# Sheet1.net
KiCad netlist of a schematic drawn in Altium Designer
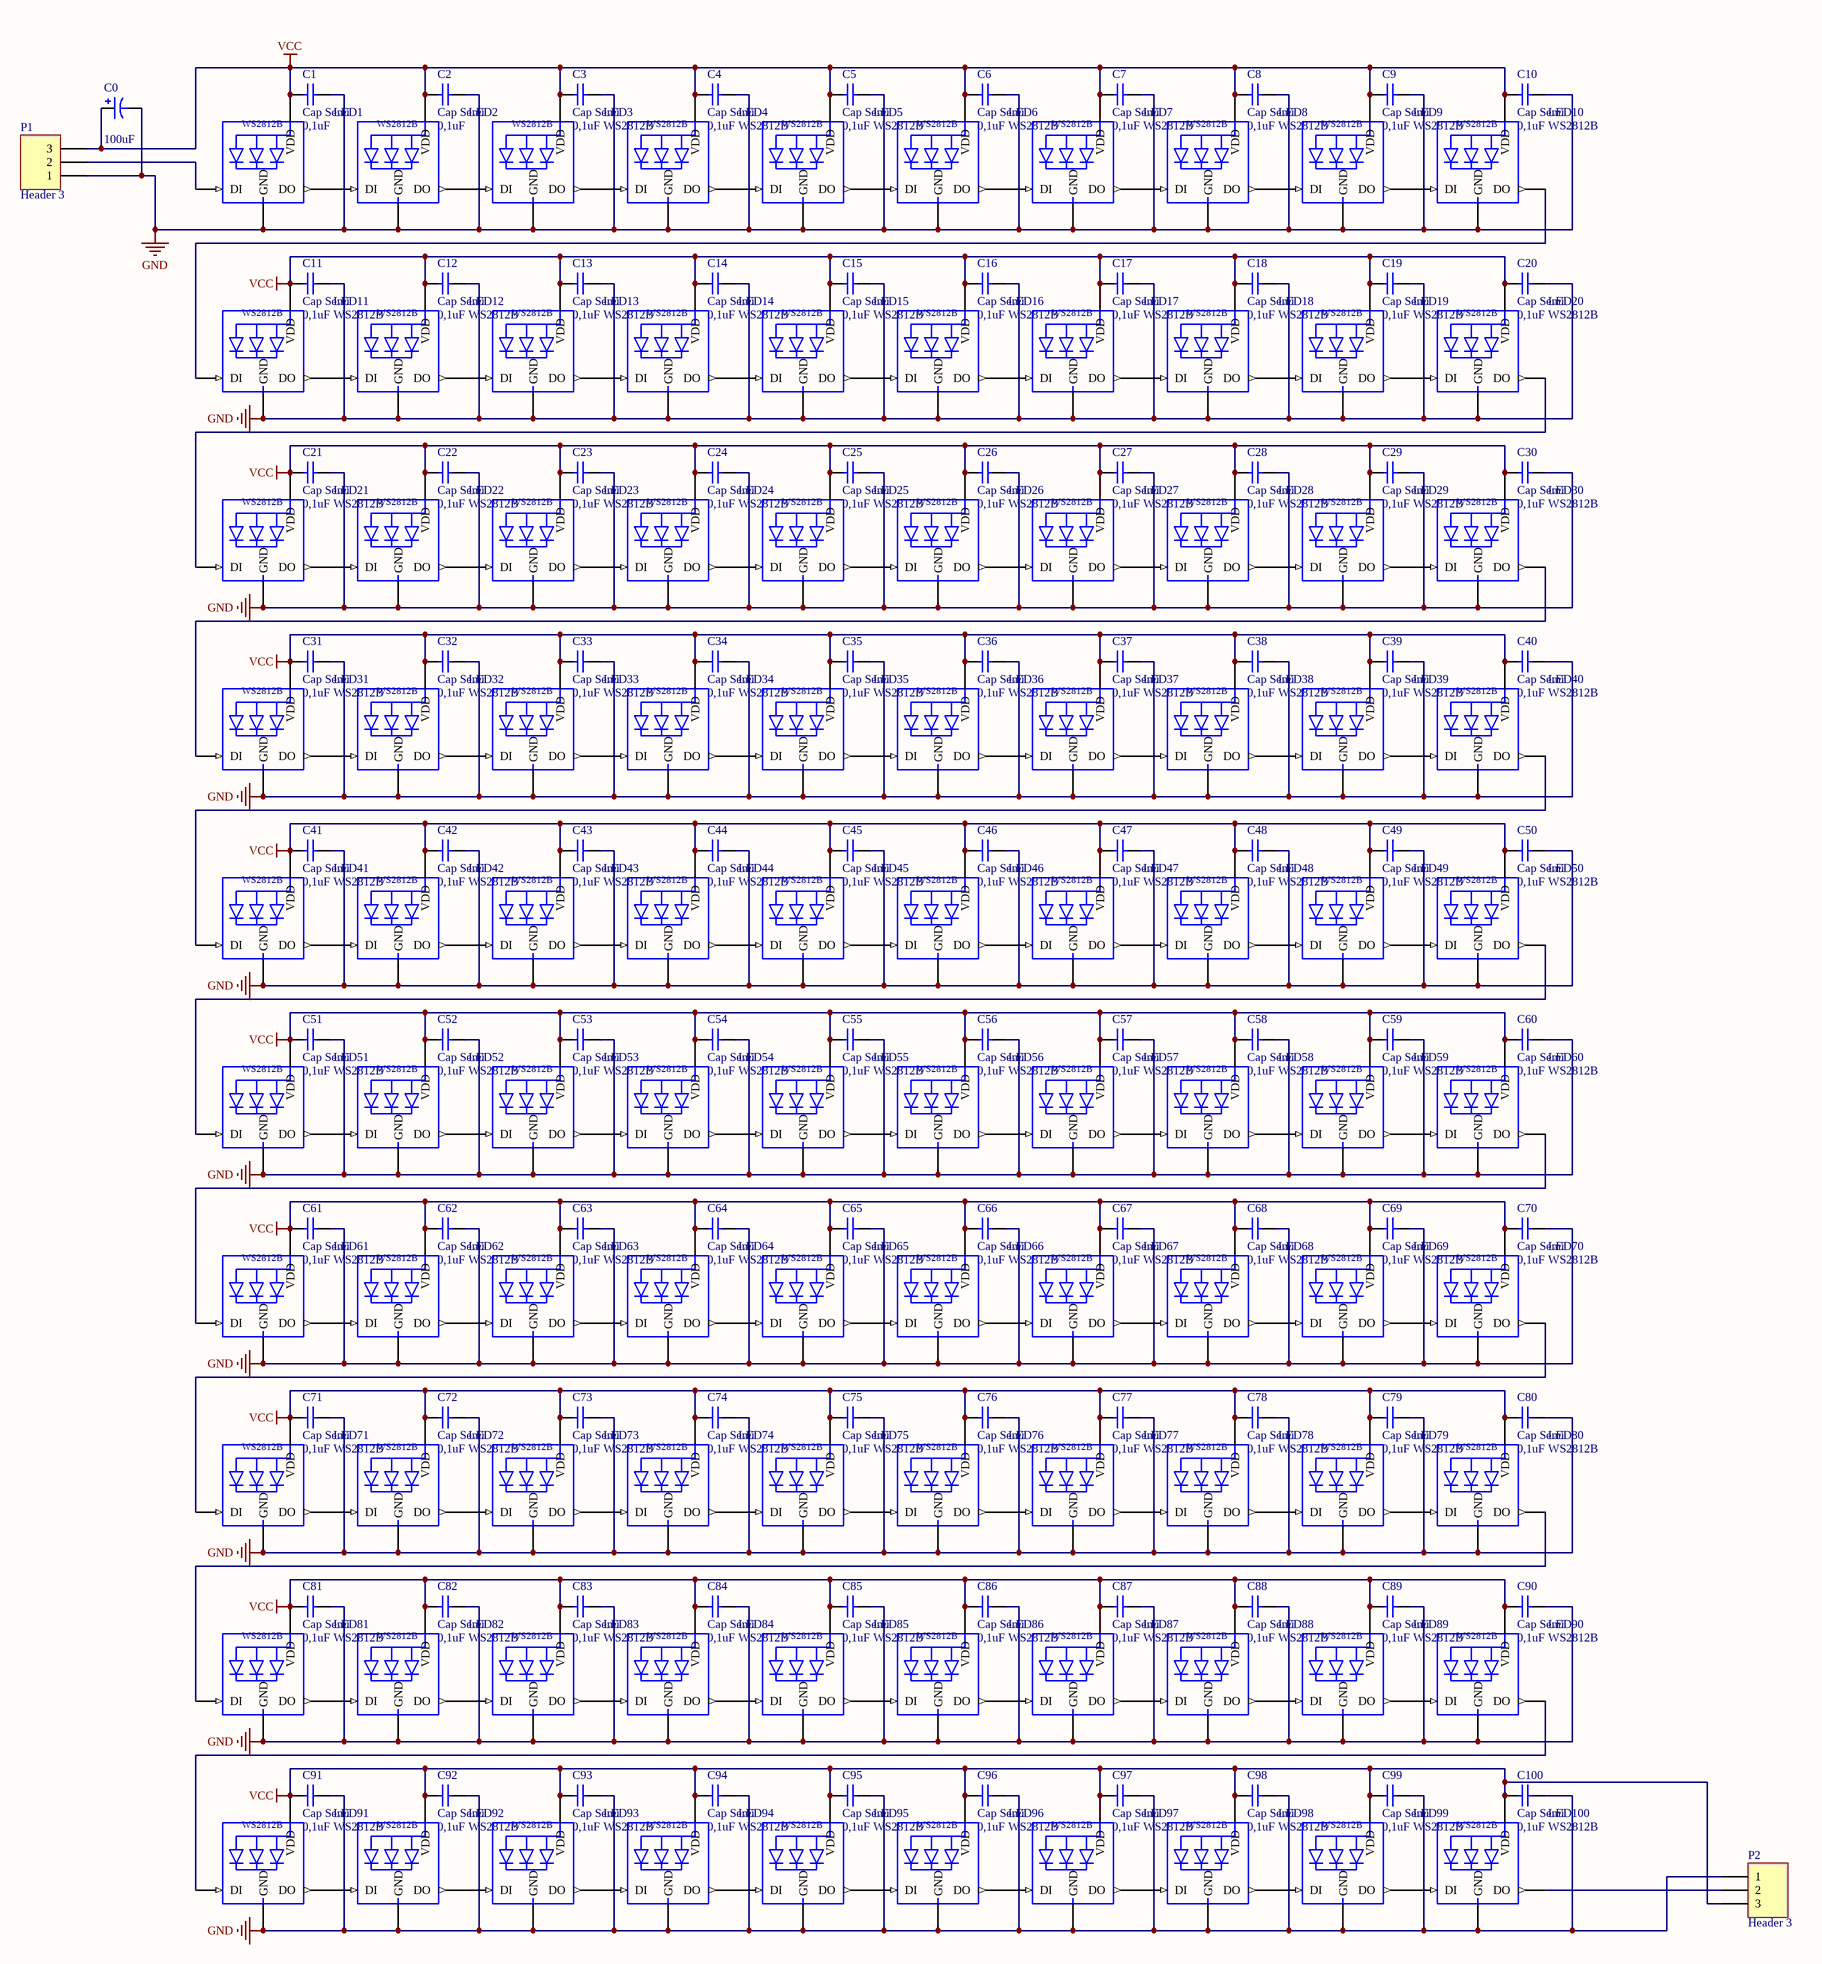
[diagram p0: Sheet1.SchDoc]

(export (version "E")
  (design (tool "Eeschema 10.0.6"))
  (components
    (comp (ref "C0")
      (value "100uF")
      (footprint "RB7.6-15")
      (description "Polarized Capacitor (Radial)")
      (fields (field (name "Comment") "Cap Pol1") (field (name "PUBLISHER") "Altium Limited"))
      (libsource (lib "Miscellaneous Devices") (part "Cap Pol1"))
    )
    (comp (ref "C1")
      (value "Cap Semi")
      (footprint "1608[0603]")
      (description "Capacitor (Semiconductor SIM Model)")
      (fields (field (name "ALTIUM_VALUE") "0,1uF") (field (name "PUBLISHER") "Altium Limited"))
      (libsource (lib "Miscellaneous Devices") (part "Cap Semi"))
    )
    (comp (ref "C2")
      (value "Cap Semi")
      (footprint "1608[0603]")
      (description "Capacitor (Semiconductor SIM Model)")
      (fields (field (name "ALTIUM_VALUE") "0,1uF") (field (name "PUBLISHER") "Altium Limited"))
      (libsource (lib "Miscellaneous Devices") (part "Cap Semi"))
    )
    (comp (ref "C3")
      (value "Cap Semi")
      (footprint "1608[0603]")
      (description "Capacitor (Semiconductor SIM Model)")
      (fields (field (name "ALTIUM_VALUE") "0,1uF") (field (name "PUBLISHER") "Altium Limited"))
      (libsource (lib "Miscellaneous Devices") (part "Cap Semi"))
    )
    (comp (ref "C4")
      (value "Cap Semi")
      (footprint "1608[0603]")
      (description "Capacitor (Semiconductor SIM Model)")
      (fields (field (name "ALTIUM_VALUE") "0,1uF") (field (name "PUBLISHER") "Altium Limited"))
      (libsource (lib "Miscellaneous Devices") (part "Cap Semi"))
    )
    (comp (ref "C5")
      (value "Cap Semi")
      (footprint "1608[0603]")
      (description "Capacitor (Semiconductor SIM Model)")
      (fields (field (name "ALTIUM_VALUE") "0,1uF") (field (name "PUBLISHER") "Altium Limited"))
      (libsource (lib "Miscellaneous Devices") (part "Cap Semi"))
    )
    (comp (ref "C6")
      (value "Cap Semi")
      (footprint "1608[0603]")
      (description "Capacitor (Semiconductor SIM Model)")
      (fields (field (name "ALTIUM_VALUE") "0,1uF") (field (name "PUBLISHER") "Altium Limited"))
      (libsource (lib "Miscellaneous Devices") (part "Cap Semi"))
    )
    (comp (ref "C7")
      (value "Cap Semi")
      (footprint "1608[0603]")
      (description "Capacitor (Semiconductor SIM Model)")
      (fields (field (name "ALTIUM_VALUE") "0,1uF") (field (name "PUBLISHER") "Altium Limited"))
      (libsource (lib "Miscellaneous Devices") (part "Cap Semi"))
    )
    (comp (ref "C8")
      (value "Cap Semi")
      (footprint "1608[0603]")
      (description "Capacitor (Semiconductor SIM Model)")
      (fields (field (name "ALTIUM_VALUE") "0,1uF") (field (name "PUBLISHER") "Altium Limited"))
      (libsource (lib "Miscellaneous Devices") (part "Cap Semi"))
    )
    (comp (ref "C9")
      (value "Cap Semi")
      (footprint "1608[0603]")
      (description "Capacitor (Semiconductor SIM Model)")
      (fields (field (name "ALTIUM_VALUE") "0,1uF") (field (name "PUBLISHER") "Altium Limited"))
      (libsource (lib "Miscellaneous Devices") (part "Cap Semi"))
    )
    (comp (ref "C10")
      (value "Cap Semi")
      (footprint "1608[0603]")
      (description "Capacitor (Semiconductor SIM Model)")
      (fields (field (name "ALTIUM_VALUE") "0,1uF") (field (name "PUBLISHER") "Altium Limited"))
      (libsource (lib "Miscellaneous Devices") (part "Cap Semi"))
    )
    (comp (ref "C11")
      (value "Cap Semi")
      (footprint "1608[0603]")
      (description "Capacitor (Semiconductor SIM Model)")
      (fields (field (name "ALTIUM_VALUE") "0,1uF") (field (name "PUBLISHER") "Altium Limited"))
      (libsource (lib "Miscellaneous Devices") (part "Cap Semi"))
    )
    (comp (ref "C12")
      (value "Cap Semi")
      (footprint "1608[0603]")
      (description "Capacitor (Semiconductor SIM Model)")
      (fields (field (name "ALTIUM_VALUE") "0,1uF") (field (name "PUBLISHER") "Altium Limited"))
      (libsource (lib "Miscellaneous Devices") (part "Cap Semi"))
    )
    (comp (ref "C13")
      (value "Cap Semi")
      (footprint "1608[0603]")
      (description "Capacitor (Semiconductor SIM Model)")
      (fields (field (name "ALTIUM_VALUE") "0,1uF") (field (name "PUBLISHER") "Altium Limited"))
      (libsource (lib "Miscellaneous Devices") (part "Cap Semi"))
    )
    (comp (ref "C14")
      (value "Cap Semi")
      (footprint "1608[0603]")
      (description "Capacitor (Semiconductor SIM Model)")
      (fields (field (name "ALTIUM_VALUE") "0,1uF") (field (name "PUBLISHER") "Altium Limited"))
      (libsource (lib "Miscellaneous Devices") (part "Cap Semi"))
    )
    (comp (ref "C15")
      (value "Cap Semi")
      (footprint "1608[0603]")
      (description "Capacitor (Semiconductor SIM Model)")
      (fields (field (name "ALTIUM_VALUE") "0,1uF") (field (name "PUBLISHER") "Altium Limited"))
      (libsource (lib "Miscellaneous Devices") (part "Cap Semi"))
    )
    (comp (ref "C16")
      (value "Cap Semi")
      (footprint "1608[0603]")
      (description "Capacitor (Semiconductor SIM Model)")
      (fields (field (name "ALTIUM_VALUE") "0,1uF") (field (name "PUBLISHER") "Altium Limited"))
      (libsource (lib "Miscellaneous Devices") (part "Cap Semi"))
    )
    (comp (ref "C17")
      (value "Cap Semi")
      (footprint "1608[0603]")
      (description "Capacitor (Semiconductor SIM Model)")
      (fields (field (name "ALTIUM_VALUE") "0,1uF") (field (name "PUBLISHER") "Altium Limited"))
      (libsource (lib "Miscellaneous Devices") (part "Cap Semi"))
    )
    (comp (ref "C18")
      (value "Cap Semi")
      (footprint "1608[0603]")
      (description "Capacitor (Semiconductor SIM Model)")
      (fields (field (name "ALTIUM_VALUE") "0,1uF") (field (name "PUBLISHER") "Altium Limited"))
      (libsource (lib "Miscellaneous Devices") (part "Cap Semi"))
    )
    (comp (ref "C19")
      (value "Cap Semi")
      (footprint "1608[0603]")
      (description "Capacitor (Semiconductor SIM Model)")
      (fields (field (name "ALTIUM_VALUE") "0,1uF") (field (name "PUBLISHER") "Altium Limited"))
      (libsource (lib "Miscellaneous Devices") (part "Cap Semi"))
    )
    (comp (ref "C20")
      (value "Cap Semi")
      (footprint "1608[0603]")
      (description "Capacitor (Semiconductor SIM Model)")
      (fields (field (name "ALTIUM_VALUE") "0,1uF") (field (name "PUBLISHER") "Altium Limited"))
      (libsource (lib "Miscellaneous Devices") (part "Cap Semi"))
    )
    (comp (ref "C21")
      (value "Cap Semi")
      (footprint "1608[0603]")
      (description "Capacitor (Semiconductor SIM Model)")
      (fields (field (name "ALTIUM_VALUE") "0,1uF") (field (name "PUBLISHER") "Altium Limited"))
      (libsource (lib "Miscellaneous Devices") (part "Cap Semi"))
    )
    (comp (ref "C22")
      (value "Cap Semi")
      (footprint "1608[0603]")
      (description "Capacitor (Semiconductor SIM Model)")
      (fields (field (name "ALTIUM_VALUE") "0,1uF") (field (name "PUBLISHER") "Altium Limited"))
      (libsource (lib "Miscellaneous Devices") (part "Cap Semi"))
    )
    (comp (ref "C23")
      (value "Cap Semi")
      (footprint "1608[0603]")
      (description "Capacitor (Semiconductor SIM Model)")
      (fields (field (name "ALTIUM_VALUE") "0,1uF") (field (name "PUBLISHER") "Altium Limited"))
      (libsource (lib "Miscellaneous Devices") (part "Cap Semi"))
    )
    (comp (ref "C24")
      (value "Cap Semi")
      (footprint "1608[0603]")
      (description "Capacitor (Semiconductor SIM Model)")
      (fields (field (name "ALTIUM_VALUE") "0,1uF") (field (name "PUBLISHER") "Altium Limited"))
      (libsource (lib "Miscellaneous Devices") (part "Cap Semi"))
    )
    (comp (ref "C25")
      (value "Cap Semi")
      (footprint "1608[0603]")
      (description "Capacitor (Semiconductor SIM Model)")
      (fields (field (name "ALTIUM_VALUE") "0,1uF") (field (name "PUBLISHER") "Altium Limited"))
      (libsource (lib "Miscellaneous Devices") (part "Cap Semi"))
    )
    (comp (ref "C26")
      (value "Cap Semi")
      (footprint "1608[0603]")
      (description "Capacitor (Semiconductor SIM Model)")
      (fields (field (name "ALTIUM_VALUE") "0,1uF") (field (name "PUBLISHER") "Altium Limited"))
      (libsource (lib "Miscellaneous Devices") (part "Cap Semi"))
    )
    (comp (ref "C27")
      (value "Cap Semi")
      (footprint "1608[0603]")
      (description "Capacitor (Semiconductor SIM Model)")
      (fields (field (name "ALTIUM_VALUE") "0,1uF") (field (name "PUBLISHER") "Altium Limited"))
      (libsource (lib "Miscellaneous Devices") (part "Cap Semi"))
    )
    (comp (ref "C28")
      (value "Cap Semi")
      (footprint "1608[0603]")
      (description "Capacitor (Semiconductor SIM Model)")
      (fields (field (name "ALTIUM_VALUE") "0,1uF") (field (name "PUBLISHER") "Altium Limited"))
      (libsource (lib "Miscellaneous Devices") (part "Cap Semi"))
    )
    (comp (ref "C29")
      (value "Cap Semi")
      (footprint "1608[0603]")
      (description "Capacitor (Semiconductor SIM Model)")
      (fields (field (name "ALTIUM_VALUE") "0,1uF") (field (name "PUBLISHER") "Altium Limited"))
      (libsource (lib "Miscellaneous Devices") (part "Cap Semi"))
    )
    (comp (ref "C30")
      (value "Cap Semi")
      (footprint "1608[0603]")
      (description "Capacitor (Semiconductor SIM Model)")
      (fields (field (name "ALTIUM_VALUE") "0,1uF") (field (name "PUBLISHER") "Altium Limited"))
      (libsource (lib "Miscellaneous Devices") (part "Cap Semi"))
    )
    (comp (ref "C31")
      (value "Cap Semi")
      (footprint "1608[0603]")
      (description "Capacitor (Semiconductor SIM Model)")
      (fields (field (name "ALTIUM_VALUE") "0,1uF") (field (name "PUBLISHER") "Altium Limited"))
      (libsource (lib "Miscellaneous Devices") (part "Cap Semi"))
    )
    (comp (ref "C32")
      (value "Cap Semi")
      (footprint "1608[0603]")
      (description "Capacitor (Semiconductor SIM Model)")
      (fields (field (name "ALTIUM_VALUE") "0,1uF") (field (name "PUBLISHER") "Altium Limited"))
      (libsource (lib "Miscellaneous Devices") (part "Cap Semi"))
    )
    (comp (ref "C33")
      (value "Cap Semi")
      (footprint "1608[0603]")
      (description "Capacitor (Semiconductor SIM Model)")
      (fields (field (name "ALTIUM_VALUE") "0,1uF") (field (name "PUBLISHER") "Altium Limited"))
      (libsource (lib "Miscellaneous Devices") (part "Cap Semi"))
    )
    (comp (ref "C34")
      (value "Cap Semi")
      (footprint "1608[0603]")
      (description "Capacitor (Semiconductor SIM Model)")
      (fields (field (name "ALTIUM_VALUE") "0,1uF") (field (name "PUBLISHER") "Altium Limited"))
      (libsource (lib "Miscellaneous Devices") (part "Cap Semi"))
    )
    (comp (ref "C35")
      (value "Cap Semi")
      (footprint "1608[0603]")
      (description "Capacitor (Semiconductor SIM Model)")
      (fields (field (name "ALTIUM_VALUE") "0,1uF") (field (name "PUBLISHER") "Altium Limited"))
      (libsource (lib "Miscellaneous Devices") (part "Cap Semi"))
    )
    (comp (ref "C36")
      (value "Cap Semi")
      (footprint "1608[0603]")
      (description "Capacitor (Semiconductor SIM Model)")
      (fields (field (name "ALTIUM_VALUE") "0,1uF") (field (name "PUBLISHER") "Altium Limited"))
      (libsource (lib "Miscellaneous Devices") (part "Cap Semi"))
    )
    (comp (ref "C37")
      (value "Cap Semi")
      (footprint "1608[0603]")
      (description "Capacitor (Semiconductor SIM Model)")
      (fields (field (name "ALTIUM_VALUE") "0,1uF") (field (name "PUBLISHER") "Altium Limited"))
      (libsource (lib "Miscellaneous Devices") (part "Cap Semi"))
    )
    (comp (ref "C38")
      (value "Cap Semi")
      (footprint "1608[0603]")
      (description "Capacitor (Semiconductor SIM Model)")
      (fields (field (name "ALTIUM_VALUE") "0,1uF") (field (name "PUBLISHER") "Altium Limited"))
      (libsource (lib "Miscellaneous Devices") (part "Cap Semi"))
    )
    (comp (ref "C39")
      (value "Cap Semi")
      (footprint "1608[0603]")
      (description "Capacitor (Semiconductor SIM Model)")
      (fields (field (name "ALTIUM_VALUE") "0,1uF") (field (name "PUBLISHER") "Altium Limited"))
      (libsource (lib "Miscellaneous Devices") (part "Cap Semi"))
    )
    (comp (ref "C40")
      (value "Cap Semi")
      (footprint "1608[0603]")
      (description "Capacitor (Semiconductor SIM Model)")
      (fields (field (name "ALTIUM_VALUE") "0,1uF") (field (name "PUBLISHER") "Altium Limited"))
      (libsource (lib "Miscellaneous Devices") (part "Cap Semi"))
    )
    (comp (ref "C41")
      (value "Cap Semi")
      (footprint "1608[0603]")
      (description "Capacitor (Semiconductor SIM Model)")
      (fields (field (name "ALTIUM_VALUE") "0,1uF") (field (name "PUBLISHER") "Altium Limited"))
      (libsource (lib "Miscellaneous Devices") (part "Cap Semi"))
    )
    (comp (ref "C42")
      (value "Cap Semi")
      (footprint "1608[0603]")
      (description "Capacitor (Semiconductor SIM Model)")
      (fields (field (name "ALTIUM_VALUE") "0,1uF") (field (name "PUBLISHER") "Altium Limited"))
      (libsource (lib "Miscellaneous Devices") (part "Cap Semi"))
    )
    (comp (ref "C43")
      (value "Cap Semi")
      (footprint "1608[0603]")
      (description "Capacitor (Semiconductor SIM Model)")
      (fields (field (name "ALTIUM_VALUE") "0,1uF") (field (name "PUBLISHER") "Altium Limited"))
      (libsource (lib "Miscellaneous Devices") (part "Cap Semi"))
    )
    (comp (ref "C44")
      (value "Cap Semi")
      (footprint "1608[0603]")
      (description "Capacitor (Semiconductor SIM Model)")
      (fields (field (name "ALTIUM_VALUE") "0,1uF") (field (name "PUBLISHER") "Altium Limited"))
      (libsource (lib "Miscellaneous Devices") (part "Cap Semi"))
    )
    (comp (ref "C45")
      (value "Cap Semi")
      (footprint "1608[0603]")
      (description "Capacitor (Semiconductor SIM Model)")
      (fields (field (name "ALTIUM_VALUE") "0,1uF") (field (name "PUBLISHER") "Altium Limited"))
      (libsource (lib "Miscellaneous Devices") (part "Cap Semi"))
    )
    (comp (ref "C46")
      (value "Cap Semi")
      (footprint "1608[0603]")
      (description "Capacitor (Semiconductor SIM Model)")
      (fields (field (name "ALTIUM_VALUE") "0,1uF") (field (name "PUBLISHER") "Altium Limited"))
      (libsource (lib "Miscellaneous Devices") (part "Cap Semi"))
    )
    (comp (ref "C47")
      (value "Cap Semi")
      (footprint "1608[0603]")
      (description "Capacitor (Semiconductor SIM Model)")
      (fields (field (name "ALTIUM_VALUE") "0,1uF") (field (name "PUBLISHER") "Altium Limited"))
      (libsource (lib "Miscellaneous Devices") (part "Cap Semi"))
    )
    (comp (ref "C48")
      (value "Cap Semi")
      (footprint "1608[0603]")
      (description "Capacitor (Semiconductor SIM Model)")
      (fields (field (name "ALTIUM_VALUE") "0,1uF") (field (name "PUBLISHER") "Altium Limited"))
      (libsource (lib "Miscellaneous Devices") (part "Cap Semi"))
    )
    (comp (ref "C49")
      (value "Cap Semi")
      (footprint "1608[0603]")
      (description "Capacitor (Semiconductor SIM Model)")
      (fields (field (name "ALTIUM_VALUE") "0,1uF") (field (name "PUBLISHER") "Altium Limited"))
      (libsource (lib "Miscellaneous Devices") (part "Cap Semi"))
    )
    (comp (ref "C50")
      (value "Cap Semi")
      (footprint "1608[0603]")
      (description "Capacitor (Semiconductor SIM Model)")
      (fields (field (name "ALTIUM_VALUE") "0,1uF") (field (name "PUBLISHER") "Altium Limited"))
      (libsource (lib "Miscellaneous Devices") (part "Cap Semi"))
    )
    (comp (ref "C51")
      (value "Cap Semi")
      (footprint "1608[0603]")
      (description "Capacitor (Semiconductor SIM Model)")
      (fields (field (name "ALTIUM_VALUE") "0,1uF") (field (name "PUBLISHER") "Altium Limited"))
      (libsource (lib "Miscellaneous Devices") (part "Cap Semi"))
    )
    (comp (ref "C52")
      (value "Cap Semi")
      (footprint "1608[0603]")
      (description "Capacitor (Semiconductor SIM Model)")
      (fields (field (name "ALTIUM_VALUE") "0,1uF") (field (name "PUBLISHER") "Altium Limited"))
      (libsource (lib "Miscellaneous Devices") (part "Cap Semi"))
    )
    (comp (ref "C53")
      (value "Cap Semi")
      (footprint "1608[0603]")
      (description "Capacitor (Semiconductor SIM Model)")
      (fields (field (name "ALTIUM_VALUE") "0,1uF") (field (name "PUBLISHER") "Altium Limited"))
      (libsource (lib "Miscellaneous Devices") (part "Cap Semi"))
    )
    (comp (ref "C54")
      (value "Cap Semi")
      (footprint "1608[0603]")
      (description "Capacitor (Semiconductor SIM Model)")
      (fields (field (name "ALTIUM_VALUE") "0,1uF") (field (name "PUBLISHER") "Altium Limited"))
      (libsource (lib "Miscellaneous Devices") (part "Cap Semi"))
    )
    (comp (ref "C55")
      (value "Cap Semi")
      (footprint "1608[0603]")
      (description "Capacitor (Semiconductor SIM Model)")
      (fields (field (name "ALTIUM_VALUE") "0,1uF") (field (name "PUBLISHER") "Altium Limited"))
      (libsource (lib "Miscellaneous Devices") (part "Cap Semi"))
    )
    (comp (ref "C56")
      (value "Cap Semi")
      (footprint "1608[0603]")
      (description "Capacitor (Semiconductor SIM Model)")
      (fields (field (name "ALTIUM_VALUE") "0,1uF") (field (name "PUBLISHER") "Altium Limited"))
      (libsource (lib "Miscellaneous Devices") (part "Cap Semi"))
    )
    (comp (ref "C57")
      (value "Cap Semi")
      (footprint "1608[0603]")
      (description "Capacitor (Semiconductor SIM Model)")
      (fields (field (name "ALTIUM_VALUE") "0,1uF") (field (name "PUBLISHER") "Altium Limited"))
      (libsource (lib "Miscellaneous Devices") (part "Cap Semi"))
    )
    (comp (ref "C58")
      (value "Cap Semi")
      (footprint "1608[0603]")
      (description "Capacitor (Semiconductor SIM Model)")
      (fields (field (name "ALTIUM_VALUE") "0,1uF") (field (name "PUBLISHER") "Altium Limited"))
      (libsource (lib "Miscellaneous Devices") (part "Cap Semi"))
    )
    (comp (ref "C59")
      (value "Cap Semi")
      (footprint "1608[0603]")
      (description "Capacitor (Semiconductor SIM Model)")
      (fields (field (name "ALTIUM_VALUE") "0,1uF") (field (name "PUBLISHER") "Altium Limited"))
      (libsource (lib "Miscellaneous Devices") (part "Cap Semi"))
    )
    (comp (ref "C60")
      (value "Cap Semi")
      (footprint "1608[0603]")
      (description "Capacitor (Semiconductor SIM Model)")
      (fields (field (name "ALTIUM_VALUE") "0,1uF") (field (name "PUBLISHER") "Altium Limited"))
      (libsource (lib "Miscellaneous Devices") (part "Cap Semi"))
    )
    (comp (ref "C61")
      (value "Cap Semi")
      (footprint "1608[0603]")
      (description "Capacitor (Semiconductor SIM Model)")
      (fields (field (name "ALTIUM_VALUE") "0,1uF") (field (name "PUBLISHER") "Altium Limited"))
      (libsource (lib "Miscellaneous Devices") (part "Cap Semi"))
    )
    (comp (ref "C62")
      (value "Cap Semi")
      (footprint "1608[0603]")
      (description "Capacitor (Semiconductor SIM Model)")
      (fields (field (name "ALTIUM_VALUE") "0,1uF") (field (name "PUBLISHER") "Altium Limited"))
      (libsource (lib "Miscellaneous Devices") (part "Cap Semi"))
    )
    (comp (ref "C63")
      (value "Cap Semi")
      (footprint "1608[0603]")
      (description "Capacitor (Semiconductor SIM Model)")
      (fields (field (name "ALTIUM_VALUE") "0,1uF") (field (name "PUBLISHER") "Altium Limited"))
      (libsource (lib "Miscellaneous Devices") (part "Cap Semi"))
    )
    (comp (ref "C64")
      (value "Cap Semi")
      (footprint "1608[0603]")
      (description "Capacitor (Semiconductor SIM Model)")
      (fields (field (name "ALTIUM_VALUE") "0,1uF") (field (name "PUBLISHER") "Altium Limited"))
      (libsource (lib "Miscellaneous Devices") (part "Cap Semi"))
    )
    (comp (ref "C65")
      (value "Cap Semi")
      (footprint "1608[0603]")
      (description "Capacitor (Semiconductor SIM Model)")
      (fields (field (name "ALTIUM_VALUE") "0,1uF") (field (name "PUBLISHER") "Altium Limited"))
      (libsource (lib "Miscellaneous Devices") (part "Cap Semi"))
    )
    (comp (ref "C66")
      (value "Cap Semi")
      (footprint "1608[0603]")
      (description "Capacitor (Semiconductor SIM Model)")
      (fields (field (name "ALTIUM_VALUE") "0,1uF") (field (name "PUBLISHER") "Altium Limited"))
      (libsource (lib "Miscellaneous Devices") (part "Cap Semi"))
    )
    (comp (ref "C67")
      (value "Cap Semi")
      (footprint "1608[0603]")
      (description "Capacitor (Semiconductor SIM Model)")
      (fields (field (name "ALTIUM_VALUE") "0,1uF") (field (name "PUBLISHER") "Altium Limited"))
      (libsource (lib "Miscellaneous Devices") (part "Cap Semi"))
    )
    (comp (ref "C68")
      (value "Cap Semi")
      (footprint "1608[0603]")
      (description "Capacitor (Semiconductor SIM Model)")
      (fields (field (name "ALTIUM_VALUE") "0,1uF") (field (name "PUBLISHER") "Altium Limited"))
      (libsource (lib "Miscellaneous Devices") (part "Cap Semi"))
    )
    (comp (ref "C69")
      (value "Cap Semi")
      (footprint "1608[0603]")
      (description "Capacitor (Semiconductor SIM Model)")
      (fields (field (name "ALTIUM_VALUE") "0,1uF") (field (name "PUBLISHER") "Altium Limited"))
      (libsource (lib "Miscellaneous Devices") (part "Cap Semi"))
    )
    (comp (ref "C70")
      (value "Cap Semi")
      (footprint "1608[0603]")
      (description "Capacitor (Semiconductor SIM Model)")
      (fields (field (name "ALTIUM_VALUE") "0,1uF") (field (name "PUBLISHER") "Altium Limited"))
      (libsource (lib "Miscellaneous Devices") (part "Cap Semi"))
    )
    (comp (ref "C71")
      (value "Cap Semi")
      (footprint "1608[0603]")
      (description "Capacitor (Semiconductor SIM Model)")
      (fields (field (name "ALTIUM_VALUE") "0,1uF") (field (name "PUBLISHER") "Altium Limited"))
      (libsource (lib "Miscellaneous Devices") (part "Cap Semi"))
    )
    (comp (ref "C72")
      (value "Cap Semi")
      (footprint "1608[0603]")
      (description "Capacitor (Semiconductor SIM Model)")
      (fields (field (name "ALTIUM_VALUE") "0,1uF") (field (name "PUBLISHER") "Altium Limited"))
      (libsource (lib "Miscellaneous Devices") (part "Cap Semi"))
    )
    (comp (ref "C73")
      (value "Cap Semi")
      (footprint "1608[0603]")
      (description "Capacitor (Semiconductor SIM Model)")
      (fields (field (name "ALTIUM_VALUE") "0,1uF") (field (name "PUBLISHER") "Altium Limited"))
      (libsource (lib "Miscellaneous Devices") (part "Cap Semi"))
    )
    (comp (ref "C74")
      (value "Cap Semi")
      (footprint "1608[0603]")
      (description "Capacitor (Semiconductor SIM Model)")
      (fields (field (name "ALTIUM_VALUE") "0,1uF") (field (name "PUBLISHER") "Altium Limited"))
      (libsource (lib "Miscellaneous Devices") (part "Cap Semi"))
    )
    (comp (ref "C75")
      (value "Cap Semi")
      (footprint "1608[0603]")
      (description "Capacitor (Semiconductor SIM Model)")
      (fields (field (name "ALTIUM_VALUE") "0,1uF") (field (name "PUBLISHER") "Altium Limited"))
      (libsource (lib "Miscellaneous Devices") (part "Cap Semi"))
    )
    (comp (ref "C76")
      (value "Cap Semi")
      (footprint "1608[0603]")
      (description "Capacitor (Semiconductor SIM Model)")
      (fields (field (name "ALTIUM_VALUE") "0,1uF") (field (name "PUBLISHER") "Altium Limited"))
      (libsource (lib "Miscellaneous Devices") (part "Cap Semi"))
    )
    (comp (ref "C77")
      (value "Cap Semi")
      (footprint "1608[0603]")
      (description "Capacitor (Semiconductor SIM Model)")
      (fields (field (name "ALTIUM_VALUE") "0,1uF") (field (name "PUBLISHER") "Altium Limited"))
      (libsource (lib "Miscellaneous Devices") (part "Cap Semi"))
    )
    (comp (ref "C78")
      (value "Cap Semi")
      (footprint "1608[0603]")
      (description "Capacitor (Semiconductor SIM Model)")
      (fields (field (name "ALTIUM_VALUE") "0,1uF") (field (name "PUBLISHER") "Altium Limited"))
      (libsource (lib "Miscellaneous Devices") (part "Cap Semi"))
    )
    (comp (ref "C79")
      (value "Cap Semi")
      (footprint "1608[0603]")
      (description "Capacitor (Semiconductor SIM Model)")
      (fields (field (name "ALTIUM_VALUE") "0,1uF") (field (name "PUBLISHER") "Altium Limited"))
      (libsource (lib "Miscellaneous Devices") (part "Cap Semi"))
    )
    (comp (ref "C80")
      (value "Cap Semi")
      (footprint "1608[0603]")
      (description "Capacitor (Semiconductor SIM Model)")
      (fields (field (name "ALTIUM_VALUE") "0,1uF") (field (name "PUBLISHER") "Altium Limited"))
      (libsource (lib "Miscellaneous Devices") (part "Cap Semi"))
    )
    (comp (ref "C81")
      (value "Cap Semi")
      (footprint "1608[0603]")
      (description "Capacitor (Semiconductor SIM Model)")
      (fields (field (name "ALTIUM_VALUE") "0,1uF") (field (name "PUBLISHER") "Altium Limited"))
      (libsource (lib "Miscellaneous Devices") (part "Cap Semi"))
    )
    (comp (ref "C82")
      (value "Cap Semi")
      (footprint "1608[0603]")
      (description "Capacitor (Semiconductor SIM Model)")
      (fields (field (name "ALTIUM_VALUE") "0,1uF") (field (name "PUBLISHER") "Altium Limited"))
      (libsource (lib "Miscellaneous Devices") (part "Cap Semi"))
    )
    (comp (ref "C83")
      (value "Cap Semi")
      (footprint "1608[0603]")
      (description "Capacitor (Semiconductor SIM Model)")
      (fields (field (name "ALTIUM_VALUE") "0,1uF") (field (name "PUBLISHER") "Altium Limited"))
      (libsource (lib "Miscellaneous Devices") (part "Cap Semi"))
    )
    (comp (ref "C84")
      (value "Cap Semi")
      (footprint "1608[0603]")
      (description "Capacitor (Semiconductor SIM Model)")
      (fields (field (name "ALTIUM_VALUE") "0,1uF") (field (name "PUBLISHER") "Altium Limited"))
      (libsource (lib "Miscellaneous Devices") (part "Cap Semi"))
    )
    (comp (ref "C85")
      (value "Cap Semi")
      (footprint "1608[0603]")
      (description "Capacitor (Semiconductor SIM Model)")
      (fields (field (name "ALTIUM_VALUE") "0,1uF") (field (name "PUBLISHER") "Altium Limited"))
      (libsource (lib "Miscellaneous Devices") (part "Cap Semi"))
    )
    (comp (ref "C86")
      (value "Cap Semi")
      (footprint "1608[0603]")
      (description "Capacitor (Semiconductor SIM Model)")
      (fields (field (name "ALTIUM_VALUE") "0,1uF") (field (name "PUBLISHER") "Altium Limited"))
      (libsource (lib "Miscellaneous Devices") (part "Cap Semi"))
    )
    (comp (ref "C87")
      (value "Cap Semi")
      (footprint "1608[0603]")
      (description "Capacitor (Semiconductor SIM Model)")
      (fields (field (name "ALTIUM_VALUE") "0,1uF") (field (name "PUBLISHER") "Altium Limited"))
      (libsource (lib "Miscellaneous Devices") (part "Cap Semi"))
    )
    (comp (ref "C88")
      (value "Cap Semi")
      (footprint "1608[0603]")
      (description "Capacitor (Semiconductor SIM Model)")
      (fields (field (name "ALTIUM_VALUE") "0,1uF") (field (name "PUBLISHER") "Altium Limited"))
      (libsource (lib "Miscellaneous Devices") (part "Cap Semi"))
    )
    (comp (ref "C89")
      (value "Cap Semi")
      (footprint "1608[0603]")
      (description "Capacitor (Semiconductor SIM Model)")
      (fields (field (name "ALTIUM_VALUE") "0,1uF") (field (name "PUBLISHER") "Altium Limited"))
      (libsource (lib "Miscellaneous Devices") (part "Cap Semi"))
    )
    (comp (ref "C90")
      (value "Cap Semi")
      (footprint "1608[0603]")
      (description "Capacitor (Semiconductor SIM Model)")
      (fields (field (name "ALTIUM_VALUE") "0,1uF") (field (name "PUBLISHER") "Altium Limited"))
      (libsource (lib "Miscellaneous Devices") (part "Cap Semi"))
    )
    (comp (ref "C91")
      (value "Cap Semi")
      (footprint "1608[0603]")
      (description "Capacitor (Semiconductor SIM Model)")
      (fields (field (name "ALTIUM_VALUE") "0,1uF") (field (name "PUBLISHER") "Altium Limited"))
      (libsource (lib "Miscellaneous Devices") (part "Cap Semi"))
    )
    (comp (ref "C92")
      (value "Cap Semi")
      (footprint "1608[0603]")
      (description "Capacitor (Semiconductor SIM Model)")
      (fields (field (name "ALTIUM_VALUE") "0,1uF") (field (name "PUBLISHER") "Altium Limited"))
      (libsource (lib "Miscellaneous Devices") (part "Cap Semi"))
    )
    (comp (ref "C93")
      (value "Cap Semi")
      (footprint "1608[0603]")
      (description "Capacitor (Semiconductor SIM Model)")
      (fields (field (name "ALTIUM_VALUE") "0,1uF") (field (name "PUBLISHER") "Altium Limited"))
      (libsource (lib "Miscellaneous Devices") (part "Cap Semi"))
    )
    (comp (ref "C94")
      (value "Cap Semi")
      (footprint "1608[0603]")
      (description "Capacitor (Semiconductor SIM Model)")
      (fields (field (name "ALTIUM_VALUE") "0,1uF") (field (name "PUBLISHER") "Altium Limited"))
      (libsource (lib "Miscellaneous Devices") (part "Cap Semi"))
    )
    (comp (ref "C95")
      (value "Cap Semi")
      (footprint "1608[0603]")
      (description "Capacitor (Semiconductor SIM Model)")
      (fields (field (name "ALTIUM_VALUE") "0,1uF") (field (name "PUBLISHER") "Altium Limited"))
      (libsource (lib "Miscellaneous Devices") (part "Cap Semi"))
    )
    (comp (ref "C96")
      (value "Cap Semi")
      (footprint "1608[0603]")
      (description "Capacitor (Semiconductor SIM Model)")
      (fields (field (name "ALTIUM_VALUE") "0,1uF") (field (name "PUBLISHER") "Altium Limited"))
      (libsource (lib "Miscellaneous Devices") (part "Cap Semi"))
    )
    (comp (ref "C97")
      (value "Cap Semi")
      (footprint "1608[0603]")
      (description "Capacitor (Semiconductor SIM Model)")
      (fields (field (name "ALTIUM_VALUE") "0,1uF") (field (name "PUBLISHER") "Altium Limited"))
      (libsource (lib "Miscellaneous Devices") (part "Cap Semi"))
    )
    (comp (ref "C98")
      (value "Cap Semi")
      (footprint "1608[0603]")
      (description "Capacitor (Semiconductor SIM Model)")
      (fields (field (name "ALTIUM_VALUE") "0,1uF") (field (name "PUBLISHER") "Altium Limited"))
      (libsource (lib "Miscellaneous Devices") (part "Cap Semi"))
    )
    (comp (ref "C99")
      (value "Cap Semi")
      (footprint "1608[0603]")
      (description "Capacitor (Semiconductor SIM Model)")
      (fields (field (name "ALTIUM_VALUE") "0,1uF") (field (name "PUBLISHER") "Altium Limited"))
      (libsource (lib "Miscellaneous Devices") (part "Cap Semi"))
    )
    (comp (ref "C100")
      (value "Cap Semi")
      (footprint "1608[0603]")
      (description "Capacitor (Semiconductor SIM Model)")
      (fields (field (name "ALTIUM_VALUE") "0,1uF") (field (name "PUBLISHER") "Altium Limited"))
      (libsource (lib "Miscellaneous Devices") (part "Cap Semi"))
    )
    (comp (ref "LED1")
      (value "WS2812B")
      (footprint "WS2812B")
      (description "Raspberry Pi HAT _40 pin_ Wheeled Robotics Kit")
      (fields (field (name "MF") "SparkFun Electronics"))
      (libsource (lib "WS2812B") (part "WS2812B"))
    )
    (comp (ref "LED2")
      (value "WS2812B")
      (footprint "WS2812B")
      (description "Raspberry Pi HAT _40 pin_ Wheeled Robotics Kit")
      (fields (field (name "MF") "SparkFun Electronics"))
      (libsource (lib "WS2812B") (part "WS2812B"))
    )
    (comp (ref "LED3")
      (value "WS2812B")
      (footprint "WS2812B")
      (description "Raspberry Pi HAT _40 pin_ Wheeled Robotics Kit")
      (fields (field (name "MF") "SparkFun Electronics"))
      (libsource (lib "WS2812B") (part "WS2812B"))
    )
    (comp (ref "LED4")
      (value "WS2812B")
      (footprint "WS2812B")
      (description "Raspberry Pi HAT _40 pin_ Wheeled Robotics Kit")
      (fields (field (name "MF") "SparkFun Electronics"))
      (libsource (lib "WS2812B") (part "WS2812B"))
    )
    (comp (ref "LED5")
      (value "WS2812B")
      (footprint "WS2812B")
      (description "Raspberry Pi HAT _40 pin_ Wheeled Robotics Kit")
      (fields (field (name "MF") "SparkFun Electronics"))
      (libsource (lib "WS2812B") (part "WS2812B"))
    )
    (comp (ref "LED6")
      (value "WS2812B")
      (footprint "WS2812B")
      (description "Raspberry Pi HAT _40 pin_ Wheeled Robotics Kit")
      (fields (field (name "MF") "SparkFun Electronics"))
      (libsource (lib "WS2812B") (part "WS2812B"))
    )
    (comp (ref "LED7")
      (value "WS2812B")
      (footprint "WS2812B")
      (description "Raspberry Pi HAT _40 pin_ Wheeled Robotics Kit")
      (fields (field (name "MF") "SparkFun Electronics"))
      (libsource (lib "WS2812B") (part "WS2812B"))
    )
    (comp (ref "LED8")
      (value "WS2812B")
      (footprint "WS2812B")
      (description "Raspberry Pi HAT _40 pin_ Wheeled Robotics Kit")
      (fields (field (name "MF") "SparkFun Electronics"))
      (libsource (lib "WS2812B") (part "WS2812B"))
    )
    (comp (ref "LED9")
      (value "WS2812B")
      (footprint "WS2812B")
      (description "Raspberry Pi HAT _40 pin_ Wheeled Robotics Kit")
      (fields (field (name "MF") "SparkFun Electronics"))
      (libsource (lib "WS2812B") (part "WS2812B"))
    )
    (comp (ref "LED10")
      (value "WS2812B")
      (footprint "WS2812B")
      (description "Raspberry Pi HAT _40 pin_ Wheeled Robotics Kit")
      (fields (field (name "MF") "SparkFun Electronics"))
      (libsource (lib "WS2812B") (part "WS2812B"))
    )
    (comp (ref "LED11")
      (value "WS2812B")
      (footprint "WS2812B")
      (description "Raspberry Pi HAT _40 pin_ Wheeled Robotics Kit")
      (fields (field (name "MF") "SparkFun Electronics"))
      (libsource (lib "WS2812B") (part "WS2812B"))
    )
    (comp (ref "LED12")
      (value "WS2812B")
      (footprint "WS2812B")
      (description "Raspberry Pi HAT _40 pin_ Wheeled Robotics Kit")
      (fields (field (name "MF") "SparkFun Electronics"))
      (libsource (lib "WS2812B") (part "WS2812B"))
    )
    (comp (ref "LED13")
      (value "WS2812B")
      (footprint "WS2812B")
      (description "Raspberry Pi HAT _40 pin_ Wheeled Robotics Kit")
      (fields (field (name "MF") "SparkFun Electronics"))
      (libsource (lib "WS2812B") (part "WS2812B"))
    )
    (comp (ref "LED14")
      (value "WS2812B")
      (footprint "WS2812B")
      (description "Raspberry Pi HAT _40 pin_ Wheeled Robotics Kit")
      (fields (field (name "MF") "SparkFun Electronics"))
      (libsource (lib "WS2812B") (part "WS2812B"))
    )
    (comp (ref "LED15")
      (value "WS2812B")
      (footprint "WS2812B")
      (description "Raspberry Pi HAT _40 pin_ Wheeled Robotics Kit")
      (fields (field (name "MF") "SparkFun Electronics"))
      (libsource (lib "WS2812B") (part "WS2812B"))
    )
    (comp (ref "LED16")
      (value "WS2812B")
      (footprint "WS2812B")
      (description "Raspberry Pi HAT _40 pin_ Wheeled Robotics Kit")
      (fields (field (name "MF") "SparkFun Electronics"))
      (libsource (lib "WS2812B") (part "WS2812B"))
    )
    (comp (ref "LED17")
      (value "WS2812B")
      (footprint "WS2812B")
      (description "Raspberry Pi HAT _40 pin_ Wheeled Robotics Kit")
      (fields (field (name "MF") "SparkFun Electronics"))
      (libsource (lib "WS2812B") (part "WS2812B"))
    )
    (comp (ref "LED18")
      (value "WS2812B")
      (footprint "WS2812B")
      (description "Raspberry Pi HAT _40 pin_ Wheeled Robotics Kit")
      (fields (field (name "MF") "SparkFun Electronics"))
      (libsource (lib "WS2812B") (part "WS2812B"))
    )
    (comp (ref "LED19")
      (value "WS2812B")
      (footprint "WS2812B")
      (description "Raspberry Pi HAT _40 pin_ Wheeled Robotics Kit")
      (fields (field (name "MF") "SparkFun Electronics"))
      (libsource (lib "WS2812B") (part "WS2812B"))
    )
    (comp (ref "LED20")
      (value "WS2812B")
      (footprint "WS2812B")
      (description "Raspberry Pi HAT _40 pin_ Wheeled Robotics Kit")
      (fields (field (name "MF") "SparkFun Electronics"))
      (libsource (lib "WS2812B") (part "WS2812B"))
    )
    (comp (ref "LED21")
      (value "WS2812B")
      (footprint "WS2812B")
      (description "Raspberry Pi HAT _40 pin_ Wheeled Robotics Kit")
      (fields (field (name "MF") "SparkFun Electronics"))
      (libsource (lib "WS2812B") (part "WS2812B"))
    )
    (comp (ref "LED22")
      (value "WS2812B")
      (footprint "WS2812B")
      (description "Raspberry Pi HAT _40 pin_ Wheeled Robotics Kit")
      (fields (field (name "MF") "SparkFun Electronics"))
      (libsource (lib "WS2812B") (part "WS2812B"))
    )
    (comp (ref "LED23")
      (value "WS2812B")
      (footprint "WS2812B")
      (description "Raspberry Pi HAT _40 pin_ Wheeled Robotics Kit")
      (fields (field (name "MF") "SparkFun Electronics"))
      (libsource (lib "WS2812B") (part "WS2812B"))
    )
    (comp (ref "LED24")
      (value "WS2812B")
      (footprint "WS2812B")
      (description "Raspberry Pi HAT _40 pin_ Wheeled Robotics Kit")
      (fields (field (name "MF") "SparkFun Electronics"))
      (libsource (lib "WS2812B") (part "WS2812B"))
    )
    (comp (ref "LED25")
      (value "WS2812B")
      (footprint "WS2812B")
      (description "Raspberry Pi HAT _40 pin_ Wheeled Robotics Kit")
      (fields (field (name "MF") "SparkFun Electronics"))
      (libsource (lib "WS2812B") (part "WS2812B"))
    )
    (comp (ref "LED26")
      (value "WS2812B")
      (footprint "WS2812B")
      (description "Raspberry Pi HAT _40 pin_ Wheeled Robotics Kit")
      (fields (field (name "MF") "SparkFun Electronics"))
      (libsource (lib "WS2812B") (part "WS2812B"))
    )
    (comp (ref "LED27")
      (value "WS2812B")
      (footprint "WS2812B")
      (description "Raspberry Pi HAT _40 pin_ Wheeled Robotics Kit")
      (fields (field (name "MF") "SparkFun Electronics"))
      (libsource (lib "WS2812B") (part "WS2812B"))
    )
    (comp (ref "LED28")
      (value "WS2812B")
      (footprint "WS2812B")
      (description "Raspberry Pi HAT _40 pin_ Wheeled Robotics Kit")
      (fields (field (name "MF") "SparkFun Electronics"))
      (libsource (lib "WS2812B") (part "WS2812B"))
    )
    (comp (ref "LED29")
      (value "WS2812B")
      (footprint "WS2812B")
      (description "Raspberry Pi HAT _40 pin_ Wheeled Robotics Kit")
      (fields (field (name "MF") "SparkFun Electronics"))
      (libsource (lib "WS2812B") (part "WS2812B"))
    )
    (comp (ref "LED30")
      (value "WS2812B")
      (footprint "WS2812B")
      (description "Raspberry Pi HAT _40 pin_ Wheeled Robotics Kit")
      (fields (field (name "MF") "SparkFun Electronics"))
      (libsource (lib "WS2812B") (part "WS2812B"))
    )
    (comp (ref "LED31")
      (value "WS2812B")
      (footprint "WS2812B")
      (description "Raspberry Pi HAT _40 pin_ Wheeled Robotics Kit")
      (fields (field (name "MF") "SparkFun Electronics"))
      (libsource (lib "WS2812B") (part "WS2812B"))
    )
    (comp (ref "LED32")
      (value "WS2812B")
      (footprint "WS2812B")
      (description "Raspberry Pi HAT _40 pin_ Wheeled Robotics Kit")
      (fields (field (name "MF") "SparkFun Electronics"))
      (libsource (lib "WS2812B") (part "WS2812B"))
    )
    (comp (ref "LED33")
      (value "WS2812B")
      (footprint "WS2812B")
      (description "Raspberry Pi HAT _40 pin_ Wheeled Robotics Kit")
      (fields (field (name "MF") "SparkFun Electronics"))
      (libsource (lib "WS2812B") (part "WS2812B"))
    )
    (comp (ref "LED34")
      (value "WS2812B")
      (footprint "WS2812B")
      (description "Raspberry Pi HAT _40 pin_ Wheeled Robotics Kit")
      (fields (field (name "MF") "SparkFun Electronics"))
      (libsource (lib "WS2812B") (part "WS2812B"))
    )
    (comp (ref "LED35")
      (value "WS2812B")
      (footprint "WS2812B")
      (description "Raspberry Pi HAT _40 pin_ Wheeled Robotics Kit")
      (fields (field (name "MF") "SparkFun Electronics"))
      (libsource (lib "WS2812B") (part "WS2812B"))
    )
    (comp (ref "LED36")
      (value "WS2812B")
      (footprint "WS2812B")
      (description "Raspberry Pi HAT _40 pin_ Wheeled Robotics Kit")
      (fields (field (name "MF") "SparkFun Electronics"))
      (libsource (lib "WS2812B") (part "WS2812B"))
    )
    (comp (ref "LED37")
      (value "WS2812B")
      (footprint "WS2812B")
      (description "Raspberry Pi HAT _40 pin_ Wheeled Robotics Kit")
      (fields (field (name "MF") "SparkFun Electronics"))
      (libsource (lib "WS2812B") (part "WS2812B"))
    )
    (comp (ref "LED38")
      (value "WS2812B")
      (footprint "WS2812B")
      (description "Raspberry Pi HAT _40 pin_ Wheeled Robotics Kit")
      (fields (field (name "MF") "SparkFun Electronics"))
      (libsource (lib "WS2812B") (part "WS2812B"))
    )
    (comp (ref "LED39")
      (value "WS2812B")
      (footprint "WS2812B")
      (description "Raspberry Pi HAT _40 pin_ Wheeled Robotics Kit")
      (fields (field (name "MF") "SparkFun Electronics"))
      (libsource (lib "WS2812B") (part "WS2812B"))
    )
    (comp (ref "LED40")
      (value "WS2812B")
      (footprint "WS2812B")
      (description "Raspberry Pi HAT _40 pin_ Wheeled Robotics Kit")
      (fields (field (name "MF") "SparkFun Electronics"))
      (libsource (lib "WS2812B") (part "WS2812B"))
    )
    (comp (ref "LED41")
      (value "WS2812B")
      (footprint "WS2812B")
      (description "Raspberry Pi HAT _40 pin_ Wheeled Robotics Kit")
      (fields (field (name "MF") "SparkFun Electronics"))
      (libsource (lib "WS2812B") (part "WS2812B"))
    )
    (comp (ref "LED42")
      (value "WS2812B")
      (footprint "WS2812B")
      (description "Raspberry Pi HAT _40 pin_ Wheeled Robotics Kit")
      (fields (field (name "MF") "SparkFun Electronics"))
      (libsource (lib "WS2812B") (part "WS2812B"))
    )
    (comp (ref "LED43")
      (value "WS2812B")
      (footprint "WS2812B")
      (description "Raspberry Pi HAT _40 pin_ Wheeled Robotics Kit")
      (fields (field (name "MF") "SparkFun Electronics"))
      (libsource (lib "WS2812B") (part "WS2812B"))
    )
    (comp (ref "LED44")
      (value "WS2812B")
      (footprint "WS2812B")
      (description "Raspberry Pi HAT _40 pin_ Wheeled Robotics Kit")
      (fields (field (name "MF") "SparkFun Electronics"))
      (libsource (lib "WS2812B") (part "WS2812B"))
    )
    (comp (ref "LED45")
      (value "WS2812B")
      (footprint "WS2812B")
      (description "Raspberry Pi HAT _40 pin_ Wheeled Robotics Kit")
      (fields (field (name "MF") "SparkFun Electronics"))
      (libsource (lib "WS2812B") (part "WS2812B"))
    )
    (comp (ref "LED46")
      (value "WS2812B")
      (footprint "WS2812B")
      (description "Raspberry Pi HAT _40 pin_ Wheeled Robotics Kit")
      (fields (field (name "MF") "SparkFun Electronics"))
      (libsource (lib "WS2812B") (part "WS2812B"))
    )
    (comp (ref "LED47")
      (value "WS2812B")
      (footprint "WS2812B")
      (description "Raspberry Pi HAT _40 pin_ Wheeled Robotics Kit")
      (fields (field (name "MF") "SparkFun Electronics"))
      (libsource (lib "WS2812B") (part "WS2812B"))
    )
    (comp (ref "LED48")
      (value "WS2812B")
      (footprint "WS2812B")
      (description "Raspberry Pi HAT _40 pin_ Wheeled Robotics Kit")
      (fields (field (name "MF") "SparkFun Electronics"))
      (libsource (lib "WS2812B") (part "WS2812B"))
    )
    (comp (ref "LED49")
      (value "WS2812B")
      (footprint "WS2812B")
      (description "Raspberry Pi HAT _40 pin_ Wheeled Robotics Kit")
      (fields (field (name "MF") "SparkFun Electronics"))
      (libsource (lib "WS2812B") (part "WS2812B"))
    )
    (comp (ref "LED50")
      (value "WS2812B")
      (footprint "WS2812B")
      (description "Raspberry Pi HAT _40 pin_ Wheeled Robotics Kit")
      (fields (field (name "MF") "SparkFun Electronics"))
      (libsource (lib "WS2812B") (part "WS2812B"))
    )
    (comp (ref "LED51")
      (value "WS2812B")
      (footprint "WS2812B")
      (description "Raspberry Pi HAT _40 pin_ Wheeled Robotics Kit")
      (fields (field (name "MF") "SparkFun Electronics"))
      (libsource (lib "WS2812B") (part "WS2812B"))
    )
    (comp (ref "LED52")
      (value "WS2812B")
      (footprint "WS2812B")
      (description "Raspberry Pi HAT _40 pin_ Wheeled Robotics Kit")
      (fields (field (name "MF") "SparkFun Electronics"))
      (libsource (lib "WS2812B") (part "WS2812B"))
    )
    (comp (ref "LED53")
      (value "WS2812B")
      (footprint "WS2812B")
      (description "Raspberry Pi HAT _40 pin_ Wheeled Robotics Kit")
      (fields (field (name "MF") "SparkFun Electronics"))
      (libsource (lib "WS2812B") (part "WS2812B"))
    )
    (comp (ref "LED54")
      (value "WS2812B")
      (footprint "WS2812B")
      (description "Raspberry Pi HAT _40 pin_ Wheeled Robotics Kit")
      (fields (field (name "MF") "SparkFun Electronics"))
      (libsource (lib "WS2812B") (part "WS2812B"))
    )
    (comp (ref "LED55")
      (value "WS2812B")
      (footprint "WS2812B")
      (description "Raspberry Pi HAT _40 pin_ Wheeled Robotics Kit")
      (fields (field (name "MF") "SparkFun Electronics"))
      (libsource (lib "WS2812B") (part "WS2812B"))
    )
    (comp (ref "LED56")
      (value "WS2812B")
      (footprint "WS2812B")
      (description "Raspberry Pi HAT _40 pin_ Wheeled Robotics Kit")
      (fields (field (name "MF") "SparkFun Electronics"))
      (libsource (lib "WS2812B") (part "WS2812B"))
    )
    (comp (ref "LED57")
      (value "WS2812B")
      (footprint "WS2812B")
      (description "Raspberry Pi HAT _40 pin_ Wheeled Robotics Kit")
      (fields (field (name "MF") "SparkFun Electronics"))
      (libsource (lib "WS2812B") (part "WS2812B"))
    )
    (comp (ref "LED58")
      (value "WS2812B")
      (footprint "WS2812B")
      (description "Raspberry Pi HAT _40 pin_ Wheeled Robotics Kit")
      (fields (field (name "MF") "SparkFun Electronics"))
      (libsource (lib "WS2812B") (part "WS2812B"))
    )
    (comp (ref "LED59")
      (value "WS2812B")
      (footprint "WS2812B")
      (description "Raspberry Pi HAT _40 pin_ Wheeled Robotics Kit")
      (fields (field (name "MF") "SparkFun Electronics"))
      (libsource (lib "WS2812B") (part "WS2812B"))
    )
    (comp (ref "LED60")
      (value "WS2812B")
      (footprint "WS2812B")
      (description "Raspberry Pi HAT _40 pin_ Wheeled Robotics Kit")
      (fields (field (name "MF") "SparkFun Electronics"))
      (libsource (lib "WS2812B") (part "WS2812B"))
    )
    (comp (ref "LED61")
      (value "WS2812B")
      (footprint "WS2812B")
      (description "Raspberry Pi HAT _40 pin_ Wheeled Robotics Kit")
      (fields (field (name "MF") "SparkFun Electronics"))
      (libsource (lib "WS2812B") (part "WS2812B"))
    )
    (comp (ref "LED62")
      (value "WS2812B")
      (footprint "WS2812B")
      (description "Raspberry Pi HAT _40 pin_ Wheeled Robotics Kit")
      (fields (field (name "MF") "SparkFun Electronics"))
      (libsource (lib "WS2812B") (part "WS2812B"))
    )
    (comp (ref "LED63")
      (value "WS2812B")
      (footprint "WS2812B")
      (description "Raspberry Pi HAT _40 pin_ Wheeled Robotics Kit")
      (fields (field (name "MF") "SparkFun Electronics"))
      (libsource (lib "WS2812B") (part "WS2812B"))
    )
    (comp (ref "LED64")
      (value "WS2812B")
      (footprint "WS2812B")
      (description "Raspberry Pi HAT _40 pin_ Wheeled Robotics Kit")
      (fields (field (name "MF") "SparkFun Electronics"))
      (libsource (lib "WS2812B") (part "WS2812B"))
    )
    (comp (ref "LED65")
      (value "WS2812B")
      (footprint "WS2812B")
      (description "Raspberry Pi HAT _40 pin_ Wheeled Robotics Kit")
      (fields (field (name "MF") "SparkFun Electronics"))
      (libsource (lib "WS2812B") (part "WS2812B"))
    )
    (comp (ref "LED66")
      (value "WS2812B")
      (footprint "WS2812B")
      (description "Raspberry Pi HAT _40 pin_ Wheeled Robotics Kit")
      (fields (field (name "MF") "SparkFun Electronics"))
      (libsource (lib "WS2812B") (part "WS2812B"))
    )
    (comp (ref "LED67")
      (value "WS2812B")
      (footprint "WS2812B")
      (description "Raspberry Pi HAT _40 pin_ Wheeled Robotics Kit")
      (fields (field (name "MF") "SparkFun Electronics"))
      (libsource (lib "WS2812B") (part "WS2812B"))
    )
    (comp (ref "LED68")
      (value "WS2812B")
      (footprint "WS2812B")
      (description "Raspberry Pi HAT _40 pin_ Wheeled Robotics Kit")
      (fields (field (name "MF") "SparkFun Electronics"))
      (libsource (lib "WS2812B") (part "WS2812B"))
    )
    (comp (ref "LED69")
      (value "WS2812B")
      (footprint "WS2812B")
      (description "Raspberry Pi HAT _40 pin_ Wheeled Robotics Kit")
      (fields (field (name "MF") "SparkFun Electronics"))
      (libsource (lib "WS2812B") (part "WS2812B"))
    )
    (comp (ref "LED70")
      (value "WS2812B")
      (footprint "WS2812B")
      (description "Raspberry Pi HAT _40 pin_ Wheeled Robotics Kit")
      (fields (field (name "MF") "SparkFun Electronics"))
      (libsource (lib "WS2812B") (part "WS2812B"))
    )
    (comp (ref "LED71")
      (value "WS2812B")
      (footprint "WS2812B")
      (description "Raspberry Pi HAT _40 pin_ Wheeled Robotics Kit")
      (fields (field (name "MF") "SparkFun Electronics"))
      (libsource (lib "WS2812B") (part "WS2812B"))
    )
    (comp (ref "LED72")
      (value "WS2812B")
      (footprint "WS2812B")
      (description "Raspberry Pi HAT _40 pin_ Wheeled Robotics Kit")
      (fields (field (name "MF") "SparkFun Electronics"))
      (libsource (lib "WS2812B") (part "WS2812B"))
    )
    (comp (ref "LED73")
      (value "WS2812B")
      (footprint "WS2812B")
      (description "Raspberry Pi HAT _40 pin_ Wheeled Robotics Kit")
      (fields (field (name "MF") "SparkFun Electronics"))
      (libsource (lib "WS2812B") (part "WS2812B"))
    )
    (comp (ref "LED74")
      (value "WS2812B")
      (footprint "WS2812B")
      (description "Raspberry Pi HAT _40 pin_ Wheeled Robotics Kit")
      (fields (field (name "MF") "SparkFun Electronics"))
      (libsource (lib "WS2812B") (part "WS2812B"))
    )
    (comp (ref "LED75")
      (value "WS2812B")
      (footprint "WS2812B")
      (description "Raspberry Pi HAT _40 pin_ Wheeled Robotics Kit")
      (fields (field (name "MF") "SparkFun Electronics"))
      (libsource (lib "WS2812B") (part "WS2812B"))
    )
    (comp (ref "LED76")
      (value "WS2812B")
      (footprint "WS2812B")
      (description "Raspberry Pi HAT _40 pin_ Wheeled Robotics Kit")
      (fields (field (name "MF") "SparkFun Electronics"))
      (libsource (lib "WS2812B") (part "WS2812B"))
    )
    (comp (ref "LED77")
      (value "WS2812B")
      (footprint "WS2812B")
      (description "Raspberry Pi HAT _40 pin_ Wheeled Robotics Kit")
      (fields (field (name "MF") "SparkFun Electronics"))
      (libsource (lib "WS2812B") (part "WS2812B"))
    )
    (comp (ref "LED78")
      (value "WS2812B")
      (footprint "WS2812B")
      (description "Raspberry Pi HAT _40 pin_ Wheeled Robotics Kit")
      (fields (field (name "MF") "SparkFun Electronics"))
      (libsource (lib "WS2812B") (part "WS2812B"))
    )
    (comp (ref "LED79")
      (value "WS2812B")
      (footprint "WS2812B")
      (description "Raspberry Pi HAT _40 pin_ Wheeled Robotics Kit")
      (fields (field (name "MF") "SparkFun Electronics"))
      (libsource (lib "WS2812B") (part "WS2812B"))
    )
    (comp (ref "LED80")
      (value "WS2812B")
      (footprint "WS2812B")
      (description "Raspberry Pi HAT _40 pin_ Wheeled Robotics Kit")
      (fields (field (name "MF") "SparkFun Electronics"))
      (libsource (lib "WS2812B") (part "WS2812B"))
    )
    (comp (ref "LED81")
      (value "WS2812B")
      (footprint "WS2812B")
      (description "Raspberry Pi HAT _40 pin_ Wheeled Robotics Kit")
      (fields (field (name "MF") "SparkFun Electronics"))
      (libsource (lib "WS2812B") (part "WS2812B"))
    )
    (comp (ref "LED82")
      (value "WS2812B")
      (footprint "WS2812B")
      (description "Raspberry Pi HAT _40 pin_ Wheeled Robotics Kit")
      (fields (field (name "MF") "SparkFun Electronics"))
      (libsource (lib "WS2812B") (part "WS2812B"))
    )
    (comp (ref "LED83")
      (value "WS2812B")
      (footprint "WS2812B")
      (description "Raspberry Pi HAT _40 pin_ Wheeled Robotics Kit")
      (fields (field (name "MF") "SparkFun Electronics"))
      (libsource (lib "WS2812B") (part "WS2812B"))
    )
    (comp (ref "LED84")
      (value "WS2812B")
      (footprint "WS2812B")
      (description "Raspberry Pi HAT _40 pin_ Wheeled Robotics Kit")
      (fields (field (name "MF") "SparkFun Electronics"))
      (libsource (lib "WS2812B") (part "WS2812B"))
    )
    (comp (ref "LED85")
      (value "WS2812B")
      (footprint "WS2812B")
      (description "Raspberry Pi HAT _40 pin_ Wheeled Robotics Kit")
      (fields (field (name "MF") "SparkFun Electronics"))
      (libsource (lib "WS2812B") (part "WS2812B"))
    )
    (comp (ref "LED86")
      (value "WS2812B")
      (footprint "WS2812B")
      (description "Raspberry Pi HAT _40 pin_ Wheeled Robotics Kit")
      (fields (field (name "MF") "SparkFun Electronics"))
      (libsource (lib "WS2812B") (part "WS2812B"))
    )
    (comp (ref "LED87")
      (value "WS2812B")
      (footprint "WS2812B")
      (description "Raspberry Pi HAT _40 pin_ Wheeled Robotics Kit")
      (fields (field (name "MF") "SparkFun Electronics"))
      (libsource (lib "WS2812B") (part "WS2812B"))
    )
    (comp (ref "LED88")
      (value "WS2812B")
      (footprint "WS2812B")
      (description "Raspberry Pi HAT _40 pin_ Wheeled Robotics Kit")
      (fields (field (name "MF") "SparkFun Electronics"))
      (libsource (lib "WS2812B") (part "WS2812B"))
    )
    (comp (ref "LED89")
      (value "WS2812B")
      (footprint "WS2812B")
      (description "Raspberry Pi HAT _40 pin_ Wheeled Robotics Kit")
      (fields (field (name "MF") "SparkFun Electronics"))
      (libsource (lib "WS2812B") (part "WS2812B"))
    )
    (comp (ref "LED90")
      (value "WS2812B")
      (footprint "WS2812B")
      (description "Raspberry Pi HAT _40 pin_ Wheeled Robotics Kit")
      (fields (field (name "MF") "SparkFun Electronics"))
      (libsource (lib "WS2812B") (part "WS2812B"))
    )
    (comp (ref "LED91")
      (value "WS2812B")
      (footprint "WS2812B")
      (description "Raspberry Pi HAT _40 pin_ Wheeled Robotics Kit")
      (fields (field (name "MF") "SparkFun Electronics"))
      (libsource (lib "WS2812B") (part "WS2812B"))
    )
    (comp (ref "LED92")
      (value "WS2812B")
      (footprint "WS2812B")
      (description "Raspberry Pi HAT _40 pin_ Wheeled Robotics Kit")
      (fields (field (name "MF") "SparkFun Electronics"))
      (libsource (lib "WS2812B") (part "WS2812B"))
    )
    (comp (ref "LED93")
      (value "WS2812B")
      (footprint "WS2812B")
      (description "Raspberry Pi HAT _40 pin_ Wheeled Robotics Kit")
      (fields (field (name "MF") "SparkFun Electronics"))
      (libsource (lib "WS2812B") (part "WS2812B"))
    )
    (comp (ref "LED94")
      (value "WS2812B")
      (footprint "WS2812B")
      (description "Raspberry Pi HAT _40 pin_ Wheeled Robotics Kit")
      (fields (field (name "MF") "SparkFun Electronics"))
      (libsource (lib "WS2812B") (part "WS2812B"))
    )
    (comp (ref "LED95")
      (value "WS2812B")
      (footprint "WS2812B")
      (description "Raspberry Pi HAT _40 pin_ Wheeled Robotics Kit")
      (fields (field (name "MF") "SparkFun Electronics"))
      (libsource (lib "WS2812B") (part "WS2812B"))
    )
    (comp (ref "LED96")
      (value "WS2812B")
      (footprint "WS2812B")
      (description "Raspberry Pi HAT _40 pin_ Wheeled Robotics Kit")
      (fields (field (name "MF") "SparkFun Electronics"))
      (libsource (lib "WS2812B") (part "WS2812B"))
    )
    (comp (ref "LED97")
      (value "WS2812B")
      (footprint "WS2812B")
      (description "Raspberry Pi HAT _40 pin_ Wheeled Robotics Kit")
      (fields (field (name "MF") "SparkFun Electronics"))
      (libsource (lib "WS2812B") (part "WS2812B"))
    )
    (comp (ref "LED98")
      (value "WS2812B")
      (footprint "WS2812B")
      (description "Raspberry Pi HAT _40 pin_ Wheeled Robotics Kit")
      (fields (field (name "MF") "SparkFun Electronics"))
      (libsource (lib "WS2812B") (part "WS2812B"))
    )
    (comp (ref "LED99")
      (value "WS2812B")
      (footprint "WS2812B")
      (description "Raspberry Pi HAT _40 pin_ Wheeled Robotics Kit")
      (fields (field (name "MF") "SparkFun Electronics"))
      (libsource (lib "WS2812B") (part "WS2812B"))
    )
    (comp (ref "LED100")
      (value "WS2812B")
      (footprint "WS2812B")
      (description "Raspberry Pi HAT _40 pin_ Wheeled Robotics Kit")
      (fields (field (name "MF") "SparkFun Electronics"))
      (libsource (lib "WS2812B") (part "WS2812B"))
    )
    (comp (ref "P1")
      (value "Header 3")
      (footprint "HDR1X3")
      (description "Header, 3-Pin")
      (fields (field (name "PUBLISHER") "Altium Limited"))
      (libsource (lib "Miscellaneous Connectors") (part "Header 3"))
    )
    (comp (ref "P2")
      (value "Header 3")
      (footprint "HDR1X3")
      (description "Header, 3-Pin")
      (fields (field (name "PUBLISHER") "Altium Limited"))
      (libsource (lib "") (part "Header 3_1"))
    )
  )
  (nets
    (net (code "1") (name "GND") (class "Default")
      (node (ref "C0") (pin "2") (pinfunction "2_2") (pintype "passive"))
      (node (ref "C1") (pin "2") (pinfunction "2_2") (pintype "passive"))
      (node (ref "C10") (pin "2") (pinfunction "2_2") (pintype "passive"))
      (node (ref "C100") (pin "2") (pinfunction "2_2") (pintype "passive"))
      (node (ref "C11") (pin "2") (pinfunction "2_2") (pintype "passive"))
      (node (ref "C12") (pin "2") (pinfunction "2_2") (pintype "passive"))
      (node (ref "C13") (pin "2") (pinfunction "2_2") (pintype "passive"))
      (node (ref "C14") (pin "2") (pinfunction "2_2") (pintype "passive"))
      (node (ref "C15") (pin "2") (pinfunction "2_2") (pintype "passive"))
      (node (ref "C16") (pin "2") (pinfunction "2_2") (pintype "passive"))
      (node (ref "C17") (pin "2") (pinfunction "2_2") (pintype "passive"))
      (node (ref "C18") (pin "2") (pinfunction "2_2") (pintype "passive"))
      (node (ref "C19") (pin "2") (pinfunction "2_2") (pintype "passive"))
      (node (ref "C2") (pin "2") (pinfunction "2_2") (pintype "passive"))
      (node (ref "C20") (pin "2") (pinfunction "2_2") (pintype "passive"))
      (node (ref "C21") (pin "2") (pinfunction "2_2") (pintype "passive"))
      (node (ref "C22") (pin "2") (pinfunction "2_2") (pintype "passive"))
      (node (ref "C23") (pin "2") (pinfunction "2_2") (pintype "passive"))
      (node (ref "C24") (pin "2") (pinfunction "2_2") (pintype "passive"))
      (node (ref "C25") (pin "2") (pinfunction "2_2") (pintype "passive"))
      (node (ref "C26") (pin "2") (pinfunction "2_2") (pintype "passive"))
      (node (ref "C27") (pin "2") (pinfunction "2_2") (pintype "passive"))
      (node (ref "C28") (pin "2") (pinfunction "2_2") (pintype "passive"))
      (node (ref "C29") (pin "2") (pinfunction "2_2") (pintype "passive"))
      (node (ref "C3") (pin "2") (pinfunction "2_2") (pintype "passive"))
      (node (ref "C30") (pin "2") (pinfunction "2_2") (pintype "passive"))
      (node (ref "C31") (pin "2") (pinfunction "2_2") (pintype "passive"))
      (node (ref "C32") (pin "2") (pinfunction "2_2") (pintype "passive"))
      (node (ref "C33") (pin "2") (pinfunction "2_2") (pintype "passive"))
      (node (ref "C34") (pin "2") (pinfunction "2_2") (pintype "passive"))
      (node (ref "C35") (pin "2") (pinfunction "2_2") (pintype "passive"))
      (node (ref "C36") (pin "2") (pinfunction "2_2") (pintype "passive"))
      (node (ref "C37") (pin "2") (pinfunction "2_2") (pintype "passive"))
      (node (ref "C38") (pin "2") (pinfunction "2_2") (pintype "passive"))
      (node (ref "C39") (pin "2") (pinfunction "2_2") (pintype "passive"))
      (node (ref "C4") (pin "2") (pinfunction "2_2") (pintype "passive"))
      (node (ref "C40") (pin "2") (pinfunction "2_2") (pintype "passive"))
      (node (ref "C41") (pin "2") (pinfunction "2_2") (pintype "passive"))
      (node (ref "C42") (pin "2") (pinfunction "2_2") (pintype "passive"))
      (node (ref "C43") (pin "2") (pinfunction "2_2") (pintype "passive"))
      (node (ref "C44") (pin "2") (pinfunction "2_2") (pintype "passive"))
      (node (ref "C45") (pin "2") (pinfunction "2_2") (pintype "passive"))
      (node (ref "C46") (pin "2") (pinfunction "2_2") (pintype "passive"))
      (node (ref "C47") (pin "2") (pinfunction "2_2") (pintype "passive"))
      (node (ref "C48") (pin "2") (pinfunction "2_2") (pintype "passive"))
      (node (ref "C49") (pin "2") (pinfunction "2_2") (pintype "passive"))
      (node (ref "C5") (pin "2") (pinfunction "2_2") (pintype "passive"))
      (node (ref "C50") (pin "2") (pinfunction "2_2") (pintype "passive"))
      (node (ref "C51") (pin "2") (pinfunction "2_2") (pintype "passive"))
      (node (ref "C52") (pin "2") (pinfunction "2_2") (pintype "passive"))
      (node (ref "C53") (pin "2") (pinfunction "2_2") (pintype "passive"))
      (node (ref "C54") (pin "2") (pinfunction "2_2") (pintype "passive"))
      (node (ref "C55") (pin "2") (pinfunction "2_2") (pintype "passive"))
      (node (ref "C56") (pin "2") (pinfunction "2_2") (pintype "passive"))
      (node (ref "C57") (pin "2") (pinfunction "2_2") (pintype "passive"))
      (node (ref "C58") (pin "2") (pinfunction "2_2") (pintype "passive"))
      (node (ref "C59") (pin "2") (pinfunction "2_2") (pintype "passive"))
      (node (ref "C6") (pin "2") (pinfunction "2_2") (pintype "passive"))
      (node (ref "C60") (pin "2") (pinfunction "2_2") (pintype "passive"))
      (node (ref "C61") (pin "2") (pinfunction "2_2") (pintype "passive"))
      (node (ref "C62") (pin "2") (pinfunction "2_2") (pintype "passive"))
      (node (ref "C63") (pin "2") (pinfunction "2_2") (pintype "passive"))
      (node (ref "C64") (pin "2") (pinfunction "2_2") (pintype "passive"))
      (node (ref "C65") (pin "2") (pinfunction "2_2") (pintype "passive"))
      (node (ref "C66") (pin "2") (pinfunction "2_2") (pintype "passive"))
      (node (ref "C67") (pin "2") (pinfunction "2_2") (pintype "passive"))
      (node (ref "C68") (pin "2") (pinfunction "2_2") (pintype "passive"))
      (node (ref "C69") (pin "2") (pinfunction "2_2") (pintype "passive"))
      (node (ref "C7") (pin "2") (pinfunction "2_2") (pintype "passive"))
      (node (ref "C70") (pin "2") (pinfunction "2_2") (pintype "passive"))
      (node (ref "C71") (pin "2") (pinfunction "2_2") (pintype "passive"))
      (node (ref "C72") (pin "2") (pinfunction "2_2") (pintype "passive"))
      (node (ref "C73") (pin "2") (pinfunction "2_2") (pintype "passive"))
      (node (ref "C74") (pin "2") (pinfunction "2_2") (pintype "passive"))
      (node (ref "C75") (pin "2") (pinfunction "2_2") (pintype "passive"))
      (node (ref "C76") (pin "2") (pinfunction "2_2") (pintype "passive"))
      (node (ref "C77") (pin "2") (pinfunction "2_2") (pintype "passive"))
      (node (ref "C78") (pin "2") (pinfunction "2_2") (pintype "passive"))
      (node (ref "C79") (pin "2") (pinfunction "2_2") (pintype "passive"))
      (node (ref "C8") (pin "2") (pinfunction "2_2") (pintype "passive"))
      (node (ref "C80") (pin "2") (pinfunction "2_2") (pintype "passive"))
      (node (ref "C81") (pin "2") (pinfunction "2_2") (pintype "passive"))
      (node (ref "C82") (pin "2") (pinfunction "2_2") (pintype "passive"))
      (node (ref "C83") (pin "2") (pinfunction "2_2") (pintype "passive"))
      (node (ref "C84") (pin "2") (pinfunction "2_2") (pintype "passive"))
      (node (ref "C85") (pin "2") (pinfunction "2_2") (pintype "passive"))
      (node (ref "C86") (pin "2") (pinfunction "2_2") (pintype "passive"))
      (node (ref "C87") (pin "2") (pinfunction "2_2") (pintype "passive"))
      (node (ref "C88") (pin "2") (pinfunction "2_2") (pintype "passive"))
      (node (ref "C89") (pin "2") (pinfunction "2_2") (pintype "passive"))
      (node (ref "C9") (pin "2") (pinfunction "2_2") (pintype "passive"))
      (node (ref "C90") (pin "2") (pinfunction "2_2") (pintype "passive"))
      (node (ref "C91") (pin "2") (pinfunction "2_2") (pintype "passive"))
      (node (ref "C92") (pin "2") (pinfunction "2_2") (pintype "passive"))
      (node (ref "C93") (pin "2") (pinfunction "2_2") (pintype "passive"))
      (node (ref "C94") (pin "2") (pinfunction "2_2") (pintype "passive"))
      (node (ref "C95") (pin "2") (pinfunction "2_2") (pintype "passive"))
      (node (ref "C96") (pin "2") (pinfunction "2_2") (pintype "passive"))
      (node (ref "C97") (pin "2") (pinfunction "2_2") (pintype "passive"))
      (node (ref "C98") (pin "2") (pinfunction "2_2") (pintype "passive"))
      (node (ref "C99") (pin "2") (pinfunction "2_2") (pintype "passive"))
      (node (ref "LED1") (pin "3-GND") (pinfunction "GND_3-GND") (pintype "power_in"))
      (node (ref "LED10") (pin "3-GND") (pinfunction "GND_3-GND") (pintype "power_in"))
      (node (ref "LED100") (pin "3-GND") (pinfunction "GND_3-GND") (pintype "power_in"))
      (node (ref "LED11") (pin "3-GND") (pinfunction "GND_3-GND") (pintype "power_in"))
      (node (ref "LED12") (pin "3-GND") (pinfunction "GND_3-GND") (pintype "power_in"))
      (node (ref "LED13") (pin "3-GND") (pinfunction "GND_3-GND") (pintype "power_in"))
      (node (ref "LED14") (pin "3-GND") (pinfunction "GND_3-GND") (pintype "power_in"))
      (node (ref "LED15") (pin "3-GND") (pinfunction "GND_3-GND") (pintype "power_in"))
      (node (ref "LED16") (pin "3-GND") (pinfunction "GND_3-GND") (pintype "power_in"))
      (node (ref "LED17") (pin "3-GND") (pinfunction "GND_3-GND") (pintype "power_in"))
      (node (ref "LED18") (pin "3-GND") (pinfunction "GND_3-GND") (pintype "power_in"))
      (node (ref "LED19") (pin "3-GND") (pinfunction "GND_3-GND") (pintype "power_in"))
      (node (ref "LED2") (pin "3-GND") (pinfunction "GND_3-GND") (pintype "power_in"))
      (node (ref "LED20") (pin "3-GND") (pinfunction "GND_3-GND") (pintype "power_in"))
      (node (ref "LED21") (pin "3-GND") (pinfunction "GND_3-GND") (pintype "power_in"))
      (node (ref "LED22") (pin "3-GND") (pinfunction "GND_3-GND") (pintype "power_in"))
      (node (ref "LED23") (pin "3-GND") (pinfunction "GND_3-GND") (pintype "power_in"))
      (node (ref "LED24") (pin "3-GND") (pinfunction "GND_3-GND") (pintype "power_in"))
      (node (ref "LED25") (pin "3-GND") (pinfunction "GND_3-GND") (pintype "power_in"))
      (node (ref "LED26") (pin "3-GND") (pinfunction "GND_3-GND") (pintype "power_in"))
      (node (ref "LED27") (pin "3-GND") (pinfunction "GND_3-GND") (pintype "power_in"))
      (node (ref "LED28") (pin "3-GND") (pinfunction "GND_3-GND") (pintype "power_in"))
      (node (ref "LED29") (pin "3-GND") (pinfunction "GND_3-GND") (pintype "power_in"))
      (node (ref "LED3") (pin "3-GND") (pinfunction "GND_3-GND") (pintype "power_in"))
      (node (ref "LED30") (pin "3-GND") (pinfunction "GND_3-GND") (pintype "power_in"))
      (node (ref "LED31") (pin "3-GND") (pinfunction "GND_3-GND") (pintype "power_in"))
      (node (ref "LED32") (pin "3-GND") (pinfunction "GND_3-GND") (pintype "power_in"))
      (node (ref "LED33") (pin "3-GND") (pinfunction "GND_3-GND") (pintype "power_in"))
      (node (ref "LED34") (pin "3-GND") (pinfunction "GND_3-GND") (pintype "power_in"))
      (node (ref "LED35") (pin "3-GND") (pinfunction "GND_3-GND") (pintype "power_in"))
      (node (ref "LED36") (pin "3-GND") (pinfunction "GND_3-GND") (pintype "power_in"))
      (node (ref "LED37") (pin "3-GND") (pinfunction "GND_3-GND") (pintype "power_in"))
      (node (ref "LED38") (pin "3-GND") (pinfunction "GND_3-GND") (pintype "power_in"))
      (node (ref "LED39") (pin "3-GND") (pinfunction "GND_3-GND") (pintype "power_in"))
      (node (ref "LED4") (pin "3-GND") (pinfunction "GND_3-GND") (pintype "power_in"))
      (node (ref "LED40") (pin "3-GND") (pinfunction "GND_3-GND") (pintype "power_in"))
      (node (ref "LED41") (pin "3-GND") (pinfunction "GND_3-GND") (pintype "power_in"))
      (node (ref "LED42") (pin "3-GND") (pinfunction "GND_3-GND") (pintype "power_in"))
      (node (ref "LED43") (pin "3-GND") (pinfunction "GND_3-GND") (pintype "power_in"))
      (node (ref "LED44") (pin "3-GND") (pinfunction "GND_3-GND") (pintype "power_in"))
      (node (ref "LED45") (pin "3-GND") (pinfunction "GND_3-GND") (pintype "power_in"))
      (node (ref "LED46") (pin "3-GND") (pinfunction "GND_3-GND") (pintype "power_in"))
      (node (ref "LED47") (pin "3-GND") (pinfunction "GND_3-GND") (pintype "power_in"))
      (node (ref "LED48") (pin "3-GND") (pinfunction "GND_3-GND") (pintype "power_in"))
      (node (ref "LED49") (pin "3-GND") (pinfunction "GND_3-GND") (pintype "power_in"))
      (node (ref "LED5") (pin "3-GND") (pinfunction "GND_3-GND") (pintype "power_in"))
      (node (ref "LED50") (pin "3-GND") (pinfunction "GND_3-GND") (pintype "power_in"))
      (node (ref "LED51") (pin "3-GND") (pinfunction "GND_3-GND") (pintype "power_in"))
      (node (ref "LED52") (pin "3-GND") (pinfunction "GND_3-GND") (pintype "power_in"))
      (node (ref "LED53") (pin "3-GND") (pinfunction "GND_3-GND") (pintype "power_in"))
      (node (ref "LED54") (pin "3-GND") (pinfunction "GND_3-GND") (pintype "power_in"))
      (node (ref "LED55") (pin "3-GND") (pinfunction "GND_3-GND") (pintype "power_in"))
      (node (ref "LED56") (pin "3-GND") (pinfunction "GND_3-GND") (pintype "power_in"))
      (node (ref "LED57") (pin "3-GND") (pinfunction "GND_3-GND") (pintype "power_in"))
      (node (ref "LED58") (pin "3-GND") (pinfunction "GND_3-GND") (pintype "power_in"))
      (node (ref "LED59") (pin "3-GND") (pinfunction "GND_3-GND") (pintype "power_in"))
      (node (ref "LED6") (pin "3-GND") (pinfunction "GND_3-GND") (pintype "power_in"))
      (node (ref "LED60") (pin "3-GND") (pinfunction "GND_3-GND") (pintype "power_in"))
      (node (ref "LED61") (pin "3-GND") (pinfunction "GND_3-GND") (pintype "power_in"))
      (node (ref "LED62") (pin "3-GND") (pinfunction "GND_3-GND") (pintype "power_in"))
      (node (ref "LED63") (pin "3-GND") (pinfunction "GND_3-GND") (pintype "power_in"))
      (node (ref "LED64") (pin "3-GND") (pinfunction "GND_3-GND") (pintype "power_in"))
      (node (ref "LED65") (pin "3-GND") (pinfunction "GND_3-GND") (pintype "power_in"))
      (node (ref "LED66") (pin "3-GND") (pinfunction "GND_3-GND") (pintype "power_in"))
      (node (ref "LED67") (pin "3-GND") (pinfunction "GND_3-GND") (pintype "power_in"))
      (node (ref "LED68") (pin "3-GND") (pinfunction "GND_3-GND") (pintype "power_in"))
      (node (ref "LED69") (pin "3-GND") (pinfunction "GND_3-GND") (pintype "power_in"))
      (node (ref "LED7") (pin "3-GND") (pinfunction "GND_3-GND") (pintype "power_in"))
      (node (ref "LED70") (pin "3-GND") (pinfunction "GND_3-GND") (pintype "power_in"))
      (node (ref "LED71") (pin "3-GND") (pinfunction "GND_3-GND") (pintype "power_in"))
      (node (ref "LED72") (pin "3-GND") (pinfunction "GND_3-GND") (pintype "power_in"))
      (node (ref "LED73") (pin "3-GND") (pinfunction "GND_3-GND") (pintype "power_in"))
      (node (ref "LED74") (pin "3-GND") (pinfunction "GND_3-GND") (pintype "power_in"))
      (node (ref "LED75") (pin "3-GND") (pinfunction "GND_3-GND") (pintype "power_in"))
      (node (ref "LED76") (pin "3-GND") (pinfunction "GND_3-GND") (pintype "power_in"))
      (node (ref "LED77") (pin "3-GND") (pinfunction "GND_3-GND") (pintype "power_in"))
      (node (ref "LED78") (pin "3-GND") (pinfunction "GND_3-GND") (pintype "power_in"))
      (node (ref "LED79") (pin "3-GND") (pinfunction "GND_3-GND") (pintype "power_in"))
      (node (ref "LED8") (pin "3-GND") (pinfunction "GND_3-GND") (pintype "power_in"))
      (node (ref "LED80") (pin "3-GND") (pinfunction "GND_3-GND") (pintype "power_in"))
      (node (ref "LED81") (pin "3-GND") (pinfunction "GND_3-GND") (pintype "power_in"))
      (node (ref "LED82") (pin "3-GND") (pinfunction "GND_3-GND") (pintype "power_in"))
      (node (ref "LED83") (pin "3-GND") (pinfunction "GND_3-GND") (pintype "power_in"))
      (node (ref "LED84") (pin "3-GND") (pinfunction "GND_3-GND") (pintype "power_in"))
      (node (ref "LED85") (pin "3-GND") (pinfunction "GND_3-GND") (pintype "power_in"))
      (node (ref "LED86") (pin "3-GND") (pinfunction "GND_3-GND") (pintype "power_in"))
      (node (ref "LED87") (pin "3-GND") (pinfunction "GND_3-GND") (pintype "power_in"))
      (node (ref "LED88") (pin "3-GND") (pinfunction "GND_3-GND") (pintype "power_in"))
      (node (ref "LED89") (pin "3-GND") (pinfunction "GND_3-GND") (pintype "power_in"))
      (node (ref "LED9") (pin "3-GND") (pinfunction "GND_3-GND") (pintype "power_in"))
      (node (ref "LED90") (pin "3-GND") (pinfunction "GND_3-GND") (pintype "power_in"))
      (node (ref "LED91") (pin "3-GND") (pinfunction "GND_3-GND") (pintype "power_in"))
      (node (ref "LED92") (pin "3-GND") (pinfunction "GND_3-GND") (pintype "power_in"))
      (node (ref "LED93") (pin "3-GND") (pinfunction "GND_3-GND") (pintype "power_in"))
      (node (ref "LED94") (pin "3-GND") (pinfunction "GND_3-GND") (pintype "power_in"))
      (node (ref "LED95") (pin "3-GND") (pinfunction "GND_3-GND") (pintype "power_in"))
      (node (ref "LED96") (pin "3-GND") (pinfunction "GND_3-GND") (pintype "power_in"))
      (node (ref "LED97") (pin "3-GND") (pinfunction "GND_3-GND") (pintype "power_in"))
      (node (ref "LED98") (pin "3-GND") (pinfunction "GND_3-GND") (pintype "power_in"))
      (node (ref "LED99") (pin "3-GND") (pinfunction "GND_3-GND") (pintype "power_in"))
      (node (ref "P1") (pin "1") (pinfunction "1_1") (pintype "passive"))
      (node (ref "P2") (pin "1") (pinfunction "1_1") (pintype "passive"))
    )
    (net (code "2") (name "Net-(LED1-DI)") (class "Default")
      (node (ref "LED1") (pin "4-DIN") (pinfunction "DI_4-DIN") (pintype "input"))
      (node (ref "P1") (pin "2") (pinfunction "2_2") (pintype "passive"))
    )
    (net (code "3") (name "Net-(LED1-DO)") (class "Default")
      (node (ref "LED1") (pin "2-DOUT") (pinfunction "DO_2-DOUT") (pintype "output"))
      (node (ref "LED2") (pin "4-DIN") (pinfunction "DI_4-DIN") (pintype "input"))
    )
    (net (code "4") (name "Net-(LED2-DO)") (class "Default")
      (node (ref "LED2") (pin "2-DOUT") (pinfunction "DO_2-DOUT") (pintype "output"))
      (node (ref "LED3") (pin "4-DIN") (pinfunction "DI_4-DIN") (pintype "input"))
    )
    (net (code "5") (name "Net-(LED3-DO)") (class "Default")
      (node (ref "LED3") (pin "2-DOUT") (pinfunction "DO_2-DOUT") (pintype "output"))
      (node (ref "LED4") (pin "4-DIN") (pinfunction "DI_4-DIN") (pintype "input"))
    )
    (net (code "6") (name "Net-(LED4-DO)") (class "Default")
      (node (ref "LED4") (pin "2-DOUT") (pinfunction "DO_2-DOUT") (pintype "output"))
      (node (ref "LED5") (pin "4-DIN") (pinfunction "DI_4-DIN") (pintype "input"))
    )
    (net (code "7") (name "Net-(LED5-DO)") (class "Default")
      (node (ref "LED5") (pin "2-DOUT") (pinfunction "DO_2-DOUT") (pintype "output"))
      (node (ref "LED6") (pin "4-DIN") (pinfunction "DI_4-DIN") (pintype "input"))
    )
    (net (code "8") (name "Net-(LED6-DO)") (class "Default")
      (node (ref "LED6") (pin "2-DOUT") (pinfunction "DO_2-DOUT") (pintype "output"))
      (node (ref "LED7") (pin "4-DIN") (pinfunction "DI_4-DIN") (pintype "input"))
    )
    (net (code "9") (name "Net-(LED7-DO)") (class "Default")
      (node (ref "LED7") (pin "2-DOUT") (pinfunction "DO_2-DOUT") (pintype "output"))
      (node (ref "LED8") (pin "4-DIN") (pinfunction "DI_4-DIN") (pintype "input"))
    )
    (net (code "10") (name "Net-(LED8-DO)") (class "Default")
      (node (ref "LED8") (pin "2-DOUT") (pinfunction "DO_2-DOUT") (pintype "output"))
      (node (ref "LED9") (pin "4-DIN") (pinfunction "DI_4-DIN") (pintype "input"))
    )
    (net (code "11") (name "Net-(LED10-DI)") (class "Default")
      (node (ref "LED10") (pin "4-DIN") (pinfunction "DI_4-DIN") (pintype "input"))
      (node (ref "LED9") (pin "2-DOUT") (pinfunction "DO_2-DOUT") (pintype "output"))
    )
    (net (code "12") (name "Net-(LED10-DO)") (class "Default")
      (node (ref "LED10") (pin "2-DOUT") (pinfunction "DO_2-DOUT") (pintype "output"))
      (node (ref "LED11") (pin "4-DIN") (pinfunction "DI_4-DIN") (pintype "input"))
    )
    (net (code "13") (name "Net-(LED11-DO)") (class "Default")
      (node (ref "LED11") (pin "2-DOUT") (pinfunction "DO_2-DOUT") (pintype "output"))
      (node (ref "LED12") (pin "4-DIN") (pinfunction "DI_4-DIN") (pintype "input"))
    )
    (net (code "14") (name "Net-(LED12-DO)") (class "Default")
      (node (ref "LED12") (pin "2-DOUT") (pinfunction "DO_2-DOUT") (pintype "output"))
      (node (ref "LED13") (pin "4-DIN") (pinfunction "DI_4-DIN") (pintype "input"))
    )
    (net (code "15") (name "Net-(LED13-DO)") (class "Default")
      (node (ref "LED13") (pin "2-DOUT") (pinfunction "DO_2-DOUT") (pintype "output"))
      (node (ref "LED14") (pin "4-DIN") (pinfunction "DI_4-DIN") (pintype "input"))
    )
    (net (code "16") (name "Net-(LED14-DO)") (class "Default")
      (node (ref "LED14") (pin "2-DOUT") (pinfunction "DO_2-DOUT") (pintype "output"))
      (node (ref "LED15") (pin "4-DIN") (pinfunction "DI_4-DIN") (pintype "input"))
    )
    (net (code "17") (name "Net-(LED15-DO)") (class "Default")
      (node (ref "LED15") (pin "2-DOUT") (pinfunction "DO_2-DOUT") (pintype "output"))
      (node (ref "LED16") (pin "4-DIN") (pinfunction "DI_4-DIN") (pintype "input"))
    )
    (net (code "18") (name "Net-(LED16-DO)") (class "Default")
      (node (ref "LED16") (pin "2-DOUT") (pinfunction "DO_2-DOUT") (pintype "output"))
      (node (ref "LED17") (pin "4-DIN") (pinfunction "DI_4-DIN") (pintype "input"))
    )
    (net (code "19") (name "Net-(LED17-DO)") (class "Default")
      (node (ref "LED17") (pin "2-DOUT") (pinfunction "DO_2-DOUT") (pintype "output"))
      (node (ref "LED18") (pin "4-DIN") (pinfunction "DI_4-DIN") (pintype "input"))
    )
    (net (code "20") (name "Net-(LED18-DO)") (class "Default")
      (node (ref "LED18") (pin "2-DOUT") (pinfunction "DO_2-DOUT") (pintype "output"))
      (node (ref "LED19") (pin "4-DIN") (pinfunction "DI_4-DIN") (pintype "input"))
    )
    (net (code "21") (name "Net-(LED19-DO)") (class "Default")
      (node (ref "LED19") (pin "2-DOUT") (pinfunction "DO_2-DOUT") (pintype "output"))
      (node (ref "LED20") (pin "4-DIN") (pinfunction "DI_4-DIN") (pintype "input"))
    )
    (net (code "22") (name "Net-(LED20-DO)") (class "Default")
      (node (ref "LED20") (pin "2-DOUT") (pinfunction "DO_2-DOUT") (pintype "output"))
      (node (ref "LED21") (pin "4-DIN") (pinfunction "DI_4-DIN") (pintype "input"))
    )
    (net (code "23") (name "Net-(LED21-DO)") (class "Default")
      (node (ref "LED21") (pin "2-DOUT") (pinfunction "DO_2-DOUT") (pintype "output"))
      (node (ref "LED22") (pin "4-DIN") (pinfunction "DI_4-DIN") (pintype "input"))
    )
    (net (code "24") (name "Net-(LED22-DO)") (class "Default")
      (node (ref "LED22") (pin "2-DOUT") (pinfunction "DO_2-DOUT") (pintype "output"))
      (node (ref "LED23") (pin "4-DIN") (pinfunction "DI_4-DIN") (pintype "input"))
    )
    (net (code "25") (name "Net-(LED23-DO)") (class "Default")
      (node (ref "LED23") (pin "2-DOUT") (pinfunction "DO_2-DOUT") (pintype "output"))
      (node (ref "LED24") (pin "4-DIN") (pinfunction "DI_4-DIN") (pintype "input"))
    )
    (net (code "26") (name "Net-(LED24-DO)") (class "Default")
      (node (ref "LED24") (pin "2-DOUT") (pinfunction "DO_2-DOUT") (pintype "output"))
      (node (ref "LED25") (pin "4-DIN") (pinfunction "DI_4-DIN") (pintype "input"))
    )
    (net (code "27") (name "Net-(LED25-DO)") (class "Default")
      (node (ref "LED25") (pin "2-DOUT") (pinfunction "DO_2-DOUT") (pintype "output"))
      (node (ref "LED26") (pin "4-DIN") (pinfunction "DI_4-DIN") (pintype "input"))
    )
    (net (code "28") (name "Net-(LED26-DO)") (class "Default")
      (node (ref "LED26") (pin "2-DOUT") (pinfunction "DO_2-DOUT") (pintype "output"))
      (node (ref "LED27") (pin "4-DIN") (pinfunction "DI_4-DIN") (pintype "input"))
    )
    (net (code "29") (name "Net-(LED27-DO)") (class "Default")
      (node (ref "LED27") (pin "2-DOUT") (pinfunction "DO_2-DOUT") (pintype "output"))
      (node (ref "LED28") (pin "4-DIN") (pinfunction "DI_4-DIN") (pintype "input"))
    )
    (net (code "30") (name "Net-(LED28-DO)") (class "Default")
      (node (ref "LED28") (pin "2-DOUT") (pinfunction "DO_2-DOUT") (pintype "output"))
      (node (ref "LED29") (pin "4-DIN") (pinfunction "DI_4-DIN") (pintype "input"))
    )
    (net (code "31") (name "Net-(LED29-DO)") (class "Default")
      (node (ref "LED29") (pin "2-DOUT") (pinfunction "DO_2-DOUT") (pintype "output"))
      (node (ref "LED30") (pin "4-DIN") (pinfunction "DI_4-DIN") (pintype "input"))
    )
    (net (code "32") (name "Net-(LED30-DO)") (class "Default")
      (node (ref "LED30") (pin "2-DOUT") (pinfunction "DO_2-DOUT") (pintype "output"))
      (node (ref "LED31") (pin "4-DIN") (pinfunction "DI_4-DIN") (pintype "input"))
    )
    (net (code "33") (name "Net-(LED31-DO)") (class "Default")
      (node (ref "LED31") (pin "2-DOUT") (pinfunction "DO_2-DOUT") (pintype "output"))
      (node (ref "LED32") (pin "4-DIN") (pinfunction "DI_4-DIN") (pintype "input"))
    )
    (net (code "34") (name "Net-(LED32-DO)") (class "Default")
      (node (ref "LED32") (pin "2-DOUT") (pinfunction "DO_2-DOUT") (pintype "output"))
      (node (ref "LED33") (pin "4-DIN") (pinfunction "DI_4-DIN") (pintype "input"))
    )
    (net (code "35") (name "Net-(LED33-DO)") (class "Default")
      (node (ref "LED33") (pin "2-DOUT") (pinfunction "DO_2-DOUT") (pintype "output"))
      (node (ref "LED34") (pin "4-DIN") (pinfunction "DI_4-DIN") (pintype "input"))
    )
    (net (code "36") (name "Net-(LED34-DO)") (class "Default")
      (node (ref "LED34") (pin "2-DOUT") (pinfunction "DO_2-DOUT") (pintype "output"))
      (node (ref "LED35") (pin "4-DIN") (pinfunction "DI_4-DIN") (pintype "input"))
    )
    (net (code "37") (name "Net-(LED35-DO)") (class "Default")
      (node (ref "LED35") (pin "2-DOUT") (pinfunction "DO_2-DOUT") (pintype "output"))
      (node (ref "LED36") (pin "4-DIN") (pinfunction "DI_4-DIN") (pintype "input"))
    )
    (net (code "38") (name "Net-(LED36-DO)") (class "Default")
      (node (ref "LED36") (pin "2-DOUT") (pinfunction "DO_2-DOUT") (pintype "output"))
      (node (ref "LED37") (pin "4-DIN") (pinfunction "DI_4-DIN") (pintype "input"))
    )
    (net (code "39") (name "Net-(LED37-DO)") (class "Default")
      (node (ref "LED37") (pin "2-DOUT") (pinfunction "DO_2-DOUT") (pintype "output"))
      (node (ref "LED38") (pin "4-DIN") (pinfunction "DI_4-DIN") (pintype "input"))
    )
    (net (code "40") (name "Net-(LED38-DO)") (class "Default")
      (node (ref "LED38") (pin "2-DOUT") (pinfunction "DO_2-DOUT") (pintype "output"))
      (node (ref "LED39") (pin "4-DIN") (pinfunction "DI_4-DIN") (pintype "input"))
    )
    (net (code "41") (name "Net-(LED39-DO)") (class "Default")
      (node (ref "LED39") (pin "2-DOUT") (pinfunction "DO_2-DOUT") (pintype "output"))
      (node (ref "LED40") (pin "4-DIN") (pinfunction "DI_4-DIN") (pintype "input"))
    )
    (net (code "42") (name "Net-(LED40-DO)") (class "Default")
      (node (ref "LED40") (pin "2-DOUT") (pinfunction "DO_2-DOUT") (pintype "output"))
      (node (ref "LED41") (pin "4-DIN") (pinfunction "DI_4-DIN") (pintype "input"))
    )
    (net (code "43") (name "Net-(LED41-DO)") (class "Default")
      (node (ref "LED41") (pin "2-DOUT") (pinfunction "DO_2-DOUT") (pintype "output"))
      (node (ref "LED42") (pin "4-DIN") (pinfunction "DI_4-DIN") (pintype "input"))
    )
    (net (code "44") (name "Net-(LED42-DO)") (class "Default")
      (node (ref "LED42") (pin "2-DOUT") (pinfunction "DO_2-DOUT") (pintype "output"))
      (node (ref "LED43") (pin "4-DIN") (pinfunction "DI_4-DIN") (pintype "input"))
    )
    (net (code "45") (name "Net-(LED43-DO)") (class "Default")
      (node (ref "LED43") (pin "2-DOUT") (pinfunction "DO_2-DOUT") (pintype "output"))
      (node (ref "LED44") (pin "4-DIN") (pinfunction "DI_4-DIN") (pintype "input"))
    )
    (net (code "46") (name "Net-(LED44-DO)") (class "Default")
      (node (ref "LED44") (pin "2-DOUT") (pinfunction "DO_2-DOUT") (pintype "output"))
      (node (ref "LED45") (pin "4-DIN") (pinfunction "DI_4-DIN") (pintype "input"))
    )
    (net (code "47") (name "Net-(LED45-DO)") (class "Default")
      (node (ref "LED45") (pin "2-DOUT") (pinfunction "DO_2-DOUT") (pintype "output"))
      (node (ref "LED46") (pin "4-DIN") (pinfunction "DI_4-DIN") (pintype "input"))
    )
    (net (code "48") (name "Net-(LED46-DO)") (class "Default")
      (node (ref "LED46") (pin "2-DOUT") (pinfunction "DO_2-DOUT") (pintype "output"))
      (node (ref "LED47") (pin "4-DIN") (pinfunction "DI_4-DIN") (pintype "input"))
    )
    (net (code "49") (name "Net-(LED47-DO)") (class "Default")
      (node (ref "LED47") (pin "2-DOUT") (pinfunction "DO_2-DOUT") (pintype "output"))
      (node (ref "LED48") (pin "4-DIN") (pinfunction "DI_4-DIN") (pintype "input"))
    )
    (net (code "50") (name "Net-(LED48-DO)") (class "Default")
      (node (ref "LED48") (pin "2-DOUT") (pinfunction "DO_2-DOUT") (pintype "output"))
      (node (ref "LED49") (pin "4-DIN") (pinfunction "DI_4-DIN") (pintype "input"))
    )
    (net (code "51") (name "Net-(LED49-DO)") (class "Default")
      (node (ref "LED49") (pin "2-DOUT") (pinfunction "DO_2-DOUT") (pintype "output"))
      (node (ref "LED50") (pin "4-DIN") (pinfunction "DI_4-DIN") (pintype "input"))
    )
    (net (code "52") (name "Net-(LED50-DO)") (class "Default")
      (node (ref "LED50") (pin "2-DOUT") (pinfunction "DO_2-DOUT") (pintype "output"))
      (node (ref "LED51") (pin "4-DIN") (pinfunction "DI_4-DIN") (pintype "input"))
    )
    (net (code "53") (name "Net-(LED51-DO)") (class "Default")
      (node (ref "LED51") (pin "2-DOUT") (pinfunction "DO_2-DOUT") (pintype "output"))
      (node (ref "LED52") (pin "4-DIN") (pinfunction "DI_4-DIN") (pintype "input"))
    )
    (net (code "54") (name "Net-(LED52-DO)") (class "Default")
      (node (ref "LED52") (pin "2-DOUT") (pinfunction "DO_2-DOUT") (pintype "output"))
      (node (ref "LED53") (pin "4-DIN") (pinfunction "DI_4-DIN") (pintype "input"))
    )
    (net (code "55") (name "Net-(LED53-DO)") (class "Default")
      (node (ref "LED53") (pin "2-DOUT") (pinfunction "DO_2-DOUT") (pintype "output"))
      (node (ref "LED54") (pin "4-DIN") (pinfunction "DI_4-DIN") (pintype "input"))
    )
    (net (code "56") (name "Net-(LED54-DO)") (class "Default")
      (node (ref "LED54") (pin "2-DOUT") (pinfunction "DO_2-DOUT") (pintype "output"))
      (node (ref "LED55") (pin "4-DIN") (pinfunction "DI_4-DIN") (pintype "input"))
    )
    (net (code "57") (name "Net-(LED55-DO)") (class "Default")
      (node (ref "LED55") (pin "2-DOUT") (pinfunction "DO_2-DOUT") (pintype "output"))
      (node (ref "LED56") (pin "4-DIN") (pinfunction "DI_4-DIN") (pintype "input"))
    )
    (net (code "58") (name "Net-(LED56-DO)") (class "Default")
      (node (ref "LED56") (pin "2-DOUT") (pinfunction "DO_2-DOUT") (pintype "output"))
      (node (ref "LED57") (pin "4-DIN") (pinfunction "DI_4-DIN") (pintype "input"))
    )
    (net (code "59") (name "Net-(LED57-DO)") (class "Default")
      (node (ref "LED57") (pin "2-DOUT") (pinfunction "DO_2-DOUT") (pintype "output"))
      (node (ref "LED58") (pin "4-DIN") (pinfunction "DI_4-DIN") (pintype "input"))
    )
    (net (code "60") (name "Net-(LED58-DO)") (class "Default")
      (node (ref "LED58") (pin "2-DOUT") (pinfunction "DO_2-DOUT") (pintype "output"))
      (node (ref "LED59") (pin "4-DIN") (pinfunction "DI_4-DIN") (pintype "input"))
    )
    (net (code "61") (name "Net-(LED59-DO)") (class "Default")
      (node (ref "LED59") (pin "2-DOUT") (pinfunction "DO_2-DOUT") (pintype "output"))
      (node (ref "LED60") (pin "4-DIN") (pinfunction "DI_4-DIN") (pintype "input"))
    )
    (net (code "62") (name "Net-(LED60-DO)") (class "Default")
      (node (ref "LED60") (pin "2-DOUT") (pinfunction "DO_2-DOUT") (pintype "output"))
      (node (ref "LED61") (pin "4-DIN") (pinfunction "DI_4-DIN") (pintype "input"))
    )
    (net (code "63") (name "Net-(LED61-DO)") (class "Default")
      (node (ref "LED61") (pin "2-DOUT") (pinfunction "DO_2-DOUT") (pintype "output"))
      (node (ref "LED62") (pin "4-DIN") (pinfunction "DI_4-DIN") (pintype "input"))
    )
    (net (code "64") (name "Net-(LED62-DO)") (class "Default")
      (node (ref "LED62") (pin "2-DOUT") (pinfunction "DO_2-DOUT") (pintype "output"))
      (node (ref "LED63") (pin "4-DIN") (pinfunction "DI_4-DIN") (pintype "input"))
    )
    (net (code "65") (name "Net-(LED63-DO)") (class "Default")
      (node (ref "LED63") (pin "2-DOUT") (pinfunction "DO_2-DOUT") (pintype "output"))
      (node (ref "LED64") (pin "4-DIN") (pinfunction "DI_4-DIN") (pintype "input"))
    )
    (net (code "66") (name "Net-(LED64-DO)") (class "Default")
      (node (ref "LED64") (pin "2-DOUT") (pinfunction "DO_2-DOUT") (pintype "output"))
      (node (ref "LED65") (pin "4-DIN") (pinfunction "DI_4-DIN") (pintype "input"))
    )
    (net (code "67") (name "Net-(LED65-DO)") (class "Default")
      (node (ref "LED65") (pin "2-DOUT") (pinfunction "DO_2-DOUT") (pintype "output"))
      (node (ref "LED66") (pin "4-DIN") (pinfunction "DI_4-DIN") (pintype "input"))
    )
    (net (code "68") (name "Net-(LED66-DO)") (class "Default")
      (node (ref "LED66") (pin "2-DOUT") (pinfunction "DO_2-DOUT") (pintype "output"))
      (node (ref "LED67") (pin "4-DIN") (pinfunction "DI_4-DIN") (pintype "input"))
    )
    (net (code "69") (name "Net-(LED67-DO)") (class "Default")
      (node (ref "LED67") (pin "2-DOUT") (pinfunction "DO_2-DOUT") (pintype "output"))
      (node (ref "LED68") (pin "4-DIN") (pinfunction "DI_4-DIN") (pintype "input"))
    )
    (net (code "70") (name "Net-(LED68-DO)") (class "Default")
      (node (ref "LED68") (pin "2-DOUT") (pinfunction "DO_2-DOUT") (pintype "output"))
      (node (ref "LED69") (pin "4-DIN") (pinfunction "DI_4-DIN") (pintype "input"))
    )
    (net (code "71") (name "Net-(LED69-DO)") (class "Default")
      (node (ref "LED69") (pin "2-DOUT") (pinfunction "DO_2-DOUT") (pintype "output"))
      (node (ref "LED70") (pin "4-DIN") (pinfunction "DI_4-DIN") (pintype "input"))
    )
    (net (code "72") (name "Net-(LED70-DO)") (class "Default")
      (node (ref "LED70") (pin "2-DOUT") (pinfunction "DO_2-DOUT") (pintype "output"))
      (node (ref "LED71") (pin "4-DIN") (pinfunction "DI_4-DIN") (pintype "input"))
    )
    (net (code "73") (name "Net-(LED71-DO)") (class "Default")
      (node (ref "LED71") (pin "2-DOUT") (pinfunction "DO_2-DOUT") (pintype "output"))
      (node (ref "LED72") (pin "4-DIN") (pinfunction "DI_4-DIN") (pintype "input"))
    )
    (net (code "74") (name "Net-(LED72-DO)") (class "Default")
      (node (ref "LED72") (pin "2-DOUT") (pinfunction "DO_2-DOUT") (pintype "output"))
      (node (ref "LED73") (pin "4-DIN") (pinfunction "DI_4-DIN") (pintype "input"))
    )
    (net (code "75") (name "Net-(LED73-DO)") (class "Default")
      (node (ref "LED73") (pin "2-DOUT") (pinfunction "DO_2-DOUT") (pintype "output"))
      (node (ref "LED74") (pin "4-DIN") (pinfunction "DI_4-DIN") (pintype "input"))
    )
    (net (code "76") (name "Net-(LED74-DO)") (class "Default")
      (node (ref "LED74") (pin "2-DOUT") (pinfunction "DO_2-DOUT") (pintype "output"))
      (node (ref "LED75") (pin "4-DIN") (pinfunction "DI_4-DIN") (pintype "input"))
    )
    (net (code "77") (name "Net-(LED75-DO)") (class "Default")
      (node (ref "LED75") (pin "2-DOUT") (pinfunction "DO_2-DOUT") (pintype "output"))
      (node (ref "LED76") (pin "4-DIN") (pinfunction "DI_4-DIN") (pintype "input"))
    )
    (net (code "78") (name "Net-(LED76-DO)") (class "Default")
      (node (ref "LED76") (pin "2-DOUT") (pinfunction "DO_2-DOUT") (pintype "output"))
      (node (ref "LED77") (pin "4-DIN") (pinfunction "DI_4-DIN") (pintype "input"))
    )
    (net (code "79") (name "Net-(LED77-DO)") (class "Default")
      (node (ref "LED77") (pin "2-DOUT") (pinfunction "DO_2-DOUT") (pintype "output"))
      (node (ref "LED78") (pin "4-DIN") (pinfunction "DI_4-DIN") (pintype "input"))
    )
    (net (code "80") (name "Net-(LED78-DO)") (class "Default")
      (node (ref "LED78") (pin "2-DOUT") (pinfunction "DO_2-DOUT") (pintype "output"))
      (node (ref "LED79") (pin "4-DIN") (pinfunction "DI_4-DIN") (pintype "input"))
    )
    (net (code "81") (name "Net-(LED79-DO)") (class "Default")
      (node (ref "LED79") (pin "2-DOUT") (pinfunction "DO_2-DOUT") (pintype "output"))
      (node (ref "LED80") (pin "4-DIN") (pinfunction "DI_4-DIN") (pintype "input"))
    )
    (net (code "82") (name "Net-(LED80-DO)") (class "Default")
      (node (ref "LED80") (pin "2-DOUT") (pinfunction "DO_2-DOUT") (pintype "output"))
      (node (ref "LED81") (pin "4-DIN") (pinfunction "DI_4-DIN") (pintype "input"))
    )
    (net (code "83") (name "Net-(LED81-DO)") (class "Default")
      (node (ref "LED81") (pin "2-DOUT") (pinfunction "DO_2-DOUT") (pintype "output"))
      (node (ref "LED82") (pin "4-DIN") (pinfunction "DI_4-DIN") (pintype "input"))
    )
    (net (code "84") (name "Net-(LED82-DO)") (class "Default")
      (node (ref "LED82") (pin "2-DOUT") (pinfunction "DO_2-DOUT") (pintype "output"))
      (node (ref "LED83") (pin "4-DIN") (pinfunction "DI_4-DIN") (pintype "input"))
    )
    (net (code "85") (name "Net-(LED83-DO)") (class "Default")
      (node (ref "LED83") (pin "2-DOUT") (pinfunction "DO_2-DOUT") (pintype "output"))
      (node (ref "LED84") (pin "4-DIN") (pinfunction "DI_4-DIN") (pintype "input"))
    )
    (net (code "86") (name "Net-(LED84-DO)") (class "Default")
      (node (ref "LED84") (pin "2-DOUT") (pinfunction "DO_2-DOUT") (pintype "output"))
      (node (ref "LED85") (pin "4-DIN") (pinfunction "DI_4-DIN") (pintype "input"))
    )
    (net (code "87") (name "Net-(LED85-DO)") (class "Default")
      (node (ref "LED85") (pin "2-DOUT") (pinfunction "DO_2-DOUT") (pintype "output"))
      (node (ref "LED86") (pin "4-DIN") (pinfunction "DI_4-DIN") (pintype "input"))
    )
    (net (code "88") (name "Net-(LED86-DO)") (class "Default")
      (node (ref "LED86") (pin "2-DOUT") (pinfunction "DO_2-DOUT") (pintype "output"))
      (node (ref "LED87") (pin "4-DIN") (pinfunction "DI_4-DIN") (pintype "input"))
    )
    (net (code "89") (name "Net-(LED87-DO)") (class "Default")
      (node (ref "LED87") (pin "2-DOUT") (pinfunction "DO_2-DOUT") (pintype "output"))
      (node (ref "LED88") (pin "4-DIN") (pinfunction "DI_4-DIN") (pintype "input"))
    )
    (net (code "90") (name "Net-(LED88-DO)") (class "Default")
      (node (ref "LED88") (pin "2-DOUT") (pinfunction "DO_2-DOUT") (pintype "output"))
      (node (ref "LED89") (pin "4-DIN") (pinfunction "DI_4-DIN") (pintype "input"))
    )
    (net (code "91") (name "Net-(LED89-DO)") (class "Default")
      (node (ref "LED89") (pin "2-DOUT") (pinfunction "DO_2-DOUT") (pintype "output"))
      (node (ref "LED90") (pin "4-DIN") (pinfunction "DI_4-DIN") (pintype "input"))
    )
    (net (code "92") (name "Net-(LED90-DO)") (class "Default")
      (node (ref "LED90") (pin "2-DOUT") (pinfunction "DO_2-DOUT") (pintype "output"))
      (node (ref "LED91") (pin "4-DIN") (pinfunction "DI_4-DIN") (pintype "input"))
    )
    (net (code "93") (name "Net-(LED91-DO)") (class "Default")
      (node (ref "LED91") (pin "2-DOUT") (pinfunction "DO_2-DOUT") (pintype "output"))
      (node (ref "LED92") (pin "4-DIN") (pinfunction "DI_4-DIN") (pintype "input"))
    )
    (net (code "94") (name "Net-(LED92-DO)") (class "Default")
      (node (ref "LED92") (pin "2-DOUT") (pinfunction "DO_2-DOUT") (pintype "output"))
      (node (ref "LED93") (pin "4-DIN") (pinfunction "DI_4-DIN") (pintype "input"))
    )
    (net (code "95") (name "Net-(LED93-DO)") (class "Default")
      (node (ref "LED93") (pin "2-DOUT") (pinfunction "DO_2-DOUT") (pintype "output"))
      (node (ref "LED94") (pin "4-DIN") (pinfunction "DI_4-DIN") (pintype "input"))
    )
    (net (code "96") (name "Net-(LED94-DO)") (class "Default")
      (node (ref "LED94") (pin "2-DOUT") (pinfunction "DO_2-DOUT") (pintype "output"))
      (node (ref "LED95") (pin "4-DIN") (pinfunction "DI_4-DIN") (pintype "input"))
    )
    (net (code "97") (name "Net-(LED95-DO)") (class "Default")
      (node (ref "LED95") (pin "2-DOUT") (pinfunction "DO_2-DOUT") (pintype "output"))
      (node (ref "LED96") (pin "4-DIN") (pinfunction "DI_4-DIN") (pintype "input"))
    )
    (net (code "98") (name "Net-(LED96-DO)") (class "Default")
      (node (ref "LED96") (pin "2-DOUT") (pinfunction "DO_2-DOUT") (pintype "output"))
      (node (ref "LED97") (pin "4-DIN") (pinfunction "DI_4-DIN") (pintype "input"))
    )
    (net (code "99") (name "Net-(LED97-DO)") (class "Default")
      (node (ref "LED97") (pin "2-DOUT") (pinfunction "DO_2-DOUT") (pintype "output"))
      (node (ref "LED98") (pin "4-DIN") (pinfunction "DI_4-DIN") (pintype "input"))
    )
    (net (code "100") (name "Net-(LED98-DO)") (class "Default")
      (node (ref "LED98") (pin "2-DOUT") (pinfunction "DO_2-DOUT") (pintype "output"))
      (node (ref "LED99") (pin "4-DIN") (pinfunction "DI_4-DIN") (pintype "input"))
    )
    (net (code "101") (name "Net-(LED100-DI)") (class "Default")
      (node (ref "LED100") (pin "4-DIN") (pinfunction "DI_4-DIN") (pintype "input"))
      (node (ref "LED99") (pin "2-DOUT") (pinfunction "DO_2-DOUT") (pintype "output"))
    )
    (net (code "102") (name "Net-(LED100-DO)") (class "Default")
      (node (ref "LED100") (pin "2-DOUT") (pinfunction "DO_2-DOUT") (pintype "output"))
      (node (ref "P2") (pin "2") (pinfunction "2_2") (pintype "passive"))
    )
    (net (code "103") (name "VCC") (class "Default")
      (node (ref "C0") (pin "1") (pinfunction "1_1") (pintype "passive"))
      (node (ref "C1") (pin "1") (pinfunction "1_1") (pintype "passive"))
      (node (ref "C10") (pin "1") (pinfunction "1_1") (pintype "passive"))
      (node (ref "C100") (pin "1") (pinfunction "1_1") (pintype "passive"))
      (node (ref "C11") (pin "1") (pinfunction "1_1") (pintype "passive"))
      (node (ref "C12") (pin "1") (pinfunction "1_1") (pintype "passive"))
      (node (ref "C13") (pin "1") (pinfunction "1_1") (pintype "passive"))
      (node (ref "C14") (pin "1") (pinfunction "1_1") (pintype "passive"))
      (node (ref "C15") (pin "1") (pinfunction "1_1") (pintype "passive"))
      (node (ref "C16") (pin "1") (pinfunction "1_1") (pintype "passive"))
      (node (ref "C17") (pin "1") (pinfunction "1_1") (pintype "passive"))
      (node (ref "C18") (pin "1") (pinfunction "1_1") (pintype "passive"))
      (node (ref "C19") (pin "1") (pinfunction "1_1") (pintype "passive"))
      (node (ref "C2") (pin "1") (pinfunction "1_1") (pintype "passive"))
      (node (ref "C20") (pin "1") (pinfunction "1_1") (pintype "passive"))
      (node (ref "C21") (pin "1") (pinfunction "1_1") (pintype "passive"))
      (node (ref "C22") (pin "1") (pinfunction "1_1") (pintype "passive"))
      (node (ref "C23") (pin "1") (pinfunction "1_1") (pintype "passive"))
      (node (ref "C24") (pin "1") (pinfunction "1_1") (pintype "passive"))
      (node (ref "C25") (pin "1") (pinfunction "1_1") (pintype "passive"))
      (node (ref "C26") (pin "1") (pinfunction "1_1") (pintype "passive"))
      (node (ref "C27") (pin "1") (pinfunction "1_1") (pintype "passive"))
      (node (ref "C28") (pin "1") (pinfunction "1_1") (pintype "passive"))
      (node (ref "C29") (pin "1") (pinfunction "1_1") (pintype "passive"))
      (node (ref "C3") (pin "1") (pinfunction "1_1") (pintype "passive"))
      (node (ref "C30") (pin "1") (pinfunction "1_1") (pintype "passive"))
      (node (ref "C31") (pin "1") (pinfunction "1_1") (pintype "passive"))
      (node (ref "C32") (pin "1") (pinfunction "1_1") (pintype "passive"))
      (node (ref "C33") (pin "1") (pinfunction "1_1") (pintype "passive"))
      (node (ref "C34") (pin "1") (pinfunction "1_1") (pintype "passive"))
      (node (ref "C35") (pin "1") (pinfunction "1_1") (pintype "passive"))
      (node (ref "C36") (pin "1") (pinfunction "1_1") (pintype "passive"))
      (node (ref "C37") (pin "1") (pinfunction "1_1") (pintype "passive"))
      (node (ref "C38") (pin "1") (pinfunction "1_1") (pintype "passive"))
      (node (ref "C39") (pin "1") (pinfunction "1_1") (pintype "passive"))
      (node (ref "C4") (pin "1") (pinfunction "1_1") (pintype "passive"))
      (node (ref "C40") (pin "1") (pinfunction "1_1") (pintype "passive"))
      (node (ref "C41") (pin "1") (pinfunction "1_1") (pintype "passive"))
      (node (ref "C42") (pin "1") (pinfunction "1_1") (pintype "passive"))
      (node (ref "C43") (pin "1") (pinfunction "1_1") (pintype "passive"))
      (node (ref "C44") (pin "1") (pinfunction "1_1") (pintype "passive"))
      (node (ref "C45") (pin "1") (pinfunction "1_1") (pintype "passive"))
      (node (ref "C46") (pin "1") (pinfunction "1_1") (pintype "passive"))
      (node (ref "C47") (pin "1") (pinfunction "1_1") (pintype "passive"))
      (node (ref "C48") (pin "1") (pinfunction "1_1") (pintype "passive"))
      (node (ref "C49") (pin "1") (pinfunction "1_1") (pintype "passive"))
      (node (ref "C5") (pin "1") (pinfunction "1_1") (pintype "passive"))
      (node (ref "C50") (pin "1") (pinfunction "1_1") (pintype "passive"))
      (node (ref "C51") (pin "1") (pinfunction "1_1") (pintype "passive"))
      (node (ref "C52") (pin "1") (pinfunction "1_1") (pintype "passive"))
      (node (ref "C53") (pin "1") (pinfunction "1_1") (pintype "passive"))
      (node (ref "C54") (pin "1") (pinfunction "1_1") (pintype "passive"))
      (node (ref "C55") (pin "1") (pinfunction "1_1") (pintype "passive"))
      (node (ref "C56") (pin "1") (pinfunction "1_1") (pintype "passive"))
      (node (ref "C57") (pin "1") (pinfunction "1_1") (pintype "passive"))
      (node (ref "C58") (pin "1") (pinfunction "1_1") (pintype "passive"))
      (node (ref "C59") (pin "1") (pinfunction "1_1") (pintype "passive"))
      (node (ref "C6") (pin "1") (pinfunction "1_1") (pintype "passive"))
      (node (ref "C60") (pin "1") (pinfunction "1_1") (pintype "passive"))
      (node (ref "C61") (pin "1") (pinfunction "1_1") (pintype "passive"))
      (node (ref "C62") (pin "1") (pinfunction "1_1") (pintype "passive"))
      (node (ref "C63") (pin "1") (pinfunction "1_1") (pintype "passive"))
      (node (ref "C64") (pin "1") (pinfunction "1_1") (pintype "passive"))
      (node (ref "C65") (pin "1") (pinfunction "1_1") (pintype "passive"))
      (node (ref "C66") (pin "1") (pinfunction "1_1") (pintype "passive"))
      (node (ref "C67") (pin "1") (pinfunction "1_1") (pintype "passive"))
      (node (ref "C68") (pin "1") (pinfunction "1_1") (pintype "passive"))
      (node (ref "C69") (pin "1") (pinfunction "1_1") (pintype "passive"))
      (node (ref "C7") (pin "1") (pinfunction "1_1") (pintype "passive"))
      (node (ref "C70") (pin "1") (pinfunction "1_1") (pintype "passive"))
      (node (ref "C71") (pin "1") (pinfunction "1_1") (pintype "passive"))
      (node (ref "C72") (pin "1") (pinfunction "1_1") (pintype "passive"))
      (node (ref "C73") (pin "1") (pinfunction "1_1") (pintype "passive"))
      (node (ref "C74") (pin "1") (pinfunction "1_1") (pintype "passive"))
      (node (ref "C75") (pin "1") (pinfunction "1_1") (pintype "passive"))
      (node (ref "C76") (pin "1") (pinfunction "1_1") (pintype "passive"))
      (node (ref "C77") (pin "1") (pinfunction "1_1") (pintype "passive"))
      (node (ref "C78") (pin "1") (pinfunction "1_1") (pintype "passive"))
      (node (ref "C79") (pin "1") (pinfunction "1_1") (pintype "passive"))
      (node (ref "C8") (pin "1") (pinfunction "1_1") (pintype "passive"))
      (node (ref "C80") (pin "1") (pinfunction "1_1") (pintype "passive"))
      (node (ref "C81") (pin "1") (pinfunction "1_1") (pintype "passive"))
      (node (ref "C82") (pin "1") (pinfunction "1_1") (pintype "passive"))
      (node (ref "C83") (pin "1") (pinfunction "1_1") (pintype "passive"))
      (node (ref "C84") (pin "1") (pinfunction "1_1") (pintype "passive"))
      (node (ref "C85") (pin "1") (pinfunction "1_1") (pintype "passive"))
      (node (ref "C86") (pin "1") (pinfunction "1_1") (pintype "passive"))
      (node (ref "C87") (pin "1") (pinfunction "1_1") (pintype "passive"))
      (node (ref "C88") (pin "1") (pinfunction "1_1") (pintype "passive"))
      (node (ref "C89") (pin "1") (pinfunction "1_1") (pintype "passive"))
      (node (ref "C9") (pin "1") (pinfunction "1_1") (pintype "passive"))
      (node (ref "C90") (pin "1") (pinfunction "1_1") (pintype "passive"))
      (node (ref "C91") (pin "1") (pinfunction "1_1") (pintype "passive"))
      (node (ref "C92") (pin "1") (pinfunction "1_1") (pintype "passive"))
      (node (ref "C93") (pin "1") (pinfunction "1_1") (pintype "passive"))
      (node (ref "C94") (pin "1") (pinfunction "1_1") (pintype "passive"))
      (node (ref "C95") (pin "1") (pinfunction "1_1") (pintype "passive"))
      (node (ref "C96") (pin "1") (pinfunction "1_1") (pintype "passive"))
      (node (ref "C97") (pin "1") (pinfunction "1_1") (pintype "passive"))
      (node (ref "C98") (pin "1") (pinfunction "1_1") (pintype "passive"))
      (node (ref "C99") (pin "1") (pinfunction "1_1") (pintype "passive"))
      (node (ref "LED1") (pin "1-VDD") (pinfunction "VDD_1-VDD") (pintype "power_in"))
      (node (ref "LED10") (pin "1-VDD") (pinfunction "VDD_1-VDD") (pintype "power_in"))
      (node (ref "LED100") (pin "1-VDD") (pinfunction "VDD_1-VDD") (pintype "power_in"))
      (node (ref "LED11") (pin "1-VDD") (pinfunction "VDD_1-VDD") (pintype "power_in"))
      (node (ref "LED12") (pin "1-VDD") (pinfunction "VDD_1-VDD") (pintype "power_in"))
      (node (ref "LED13") (pin "1-VDD") (pinfunction "VDD_1-VDD") (pintype "power_in"))
      (node (ref "LED14") (pin "1-VDD") (pinfunction "VDD_1-VDD") (pintype "power_in"))
      (node (ref "LED15") (pin "1-VDD") (pinfunction "VDD_1-VDD") (pintype "power_in"))
      (node (ref "LED16") (pin "1-VDD") (pinfunction "VDD_1-VDD") (pintype "power_in"))
      (node (ref "LED17") (pin "1-VDD") (pinfunction "VDD_1-VDD") (pintype "power_in"))
      (node (ref "LED18") (pin "1-VDD") (pinfunction "VDD_1-VDD") (pintype "power_in"))
      (node (ref "LED19") (pin "1-VDD") (pinfunction "VDD_1-VDD") (pintype "power_in"))
      (node (ref "LED2") (pin "1-VDD") (pinfunction "VDD_1-VDD") (pintype "power_in"))
      (node (ref "LED20") (pin "1-VDD") (pinfunction "VDD_1-VDD") (pintype "power_in"))
      (node (ref "LED21") (pin "1-VDD") (pinfunction "VDD_1-VDD") (pintype "power_in"))
      (node (ref "LED22") (pin "1-VDD") (pinfunction "VDD_1-VDD") (pintype "power_in"))
      (node (ref "LED23") (pin "1-VDD") (pinfunction "VDD_1-VDD") (pintype "power_in"))
      (node (ref "LED24") (pin "1-VDD") (pinfunction "VDD_1-VDD") (pintype "power_in"))
      (node (ref "LED25") (pin "1-VDD") (pinfunction "VDD_1-VDD") (pintype "power_in"))
      (node (ref "LED26") (pin "1-VDD") (pinfunction "VDD_1-VDD") (pintype "power_in"))
      (node (ref "LED27") (pin "1-VDD") (pinfunction "VDD_1-VDD") (pintype "power_in"))
      (node (ref "LED28") (pin "1-VDD") (pinfunction "VDD_1-VDD") (pintype "power_in"))
      (node (ref "LED29") (pin "1-VDD") (pinfunction "VDD_1-VDD") (pintype "power_in"))
      (node (ref "LED3") (pin "1-VDD") (pinfunction "VDD_1-VDD") (pintype "power_in"))
      (node (ref "LED30") (pin "1-VDD") (pinfunction "VDD_1-VDD") (pintype "power_in"))
      (node (ref "LED31") (pin "1-VDD") (pinfunction "VDD_1-VDD") (pintype "power_in"))
      (node (ref "LED32") (pin "1-VDD") (pinfunction "VDD_1-VDD") (pintype "power_in"))
      (node (ref "LED33") (pin "1-VDD") (pinfunction "VDD_1-VDD") (pintype "power_in"))
      (node (ref "LED34") (pin "1-VDD") (pinfunction "VDD_1-VDD") (pintype "power_in"))
      (node (ref "LED35") (pin "1-VDD") (pinfunction "VDD_1-VDD") (pintype "power_in"))
      (node (ref "LED36") (pin "1-VDD") (pinfunction "VDD_1-VDD") (pintype "power_in"))
      (node (ref "LED37") (pin "1-VDD") (pinfunction "VDD_1-VDD") (pintype "power_in"))
      (node (ref "LED38") (pin "1-VDD") (pinfunction "VDD_1-VDD") (pintype "power_in"))
      (node (ref "LED39") (pin "1-VDD") (pinfunction "VDD_1-VDD") (pintype "power_in"))
      (node (ref "LED4") (pin "1-VDD") (pinfunction "VDD_1-VDD") (pintype "power_in"))
      (node (ref "LED40") (pin "1-VDD") (pinfunction "VDD_1-VDD") (pintype "power_in"))
      (node (ref "LED41") (pin "1-VDD") (pinfunction "VDD_1-VDD") (pintype "power_in"))
      (node (ref "LED42") (pin "1-VDD") (pinfunction "VDD_1-VDD") (pintype "power_in"))
      (node (ref "LED43") (pin "1-VDD") (pinfunction "VDD_1-VDD") (pintype "power_in"))
      (node (ref "LED44") (pin "1-VDD") (pinfunction "VDD_1-VDD") (pintype "power_in"))
      (node (ref "LED45") (pin "1-VDD") (pinfunction "VDD_1-VDD") (pintype "power_in"))
      (node (ref "LED46") (pin "1-VDD") (pinfunction "VDD_1-VDD") (pintype "power_in"))
      (node (ref "LED47") (pin "1-VDD") (pinfunction "VDD_1-VDD") (pintype "power_in"))
      (node (ref "LED48") (pin "1-VDD") (pinfunction "VDD_1-VDD") (pintype "power_in"))
      (node (ref "LED49") (pin "1-VDD") (pinfunction "VDD_1-VDD") (pintype "power_in"))
      (node (ref "LED5") (pin "1-VDD") (pinfunction "VDD_1-VDD") (pintype "power_in"))
      (node (ref "LED50") (pin "1-VDD") (pinfunction "VDD_1-VDD") (pintype "power_in"))
      (node (ref "LED51") (pin "1-VDD") (pinfunction "VDD_1-VDD") (pintype "power_in"))
      (node (ref "LED52") (pin "1-VDD") (pinfunction "VDD_1-VDD") (pintype "power_in"))
      (node (ref "LED53") (pin "1-VDD") (pinfunction "VDD_1-VDD") (pintype "power_in"))
      (node (ref "LED54") (pin "1-VDD") (pinfunction "VDD_1-VDD") (pintype "power_in"))
      (node (ref "LED55") (pin "1-VDD") (pinfunction "VDD_1-VDD") (pintype "power_in"))
      (node (ref "LED56") (pin "1-VDD") (pinfunction "VDD_1-VDD") (pintype "power_in"))
      (node (ref "LED57") (pin "1-VDD") (pinfunction "VDD_1-VDD") (pintype "power_in"))
      (node (ref "LED58") (pin "1-VDD") (pinfunction "VDD_1-VDD") (pintype "power_in"))
      (node (ref "LED59") (pin "1-VDD") (pinfunction "VDD_1-VDD") (pintype "power_in"))
      (node (ref "LED6") (pin "1-VDD") (pinfunction "VDD_1-VDD") (pintype "power_in"))
      (node (ref "LED60") (pin "1-VDD") (pinfunction "VDD_1-VDD") (pintype "power_in"))
      (node (ref "LED61") (pin "1-VDD") (pinfunction "VDD_1-VDD") (pintype "power_in"))
      (node (ref "LED62") (pin "1-VDD") (pinfunction "VDD_1-VDD") (pintype "power_in"))
      (node (ref "LED63") (pin "1-VDD") (pinfunction "VDD_1-VDD") (pintype "power_in"))
      (node (ref "LED64") (pin "1-VDD") (pinfunction "VDD_1-VDD") (pintype "power_in"))
      (node (ref "LED65") (pin "1-VDD") (pinfunction "VDD_1-VDD") (pintype "power_in"))
      (node (ref "LED66") (pin "1-VDD") (pinfunction "VDD_1-VDD") (pintype "power_in"))
      (node (ref "LED67") (pin "1-VDD") (pinfunction "VDD_1-VDD") (pintype "power_in"))
      (node (ref "LED68") (pin "1-VDD") (pinfunction "VDD_1-VDD") (pintype "power_in"))
      (node (ref "LED69") (pin "1-VDD") (pinfunction "VDD_1-VDD") (pintype "power_in"))
      (node (ref "LED7") (pin "1-VDD") (pinfunction "VDD_1-VDD") (pintype "power_in"))
      (node (ref "LED70") (pin "1-VDD") (pinfunction "VDD_1-VDD") (pintype "power_in"))
      (node (ref "LED71") (pin "1-VDD") (pinfunction "VDD_1-VDD") (pintype "power_in"))
      (node (ref "LED72") (pin "1-VDD") (pinfunction "VDD_1-VDD") (pintype "power_in"))
      (node (ref "LED73") (pin "1-VDD") (pinfunction "VDD_1-VDD") (pintype "power_in"))
      (node (ref "LED74") (pin "1-VDD") (pinfunction "VDD_1-VDD") (pintype "power_in"))
      (node (ref "LED75") (pin "1-VDD") (pinfunction "VDD_1-VDD") (pintype "power_in"))
      (node (ref "LED76") (pin "1-VDD") (pinfunction "VDD_1-VDD") (pintype "power_in"))
      (node (ref "LED77") (pin "1-VDD") (pinfunction "VDD_1-VDD") (pintype "power_in"))
      (node (ref "LED78") (pin "1-VDD") (pinfunction "VDD_1-VDD") (pintype "power_in"))
      (node (ref "LED79") (pin "1-VDD") (pinfunction "VDD_1-VDD") (pintype "power_in"))
      (node (ref "LED8") (pin "1-VDD") (pinfunction "VDD_1-VDD") (pintype "power_in"))
      (node (ref "LED80") (pin "1-VDD") (pinfunction "VDD_1-VDD") (pintype "power_in"))
      (node (ref "LED81") (pin "1-VDD") (pinfunction "VDD_1-VDD") (pintype "power_in"))
      (node (ref "LED82") (pin "1-VDD") (pinfunction "VDD_1-VDD") (pintype "power_in"))
      (node (ref "LED83") (pin "1-VDD") (pinfunction "VDD_1-VDD") (pintype "power_in"))
      (node (ref "LED84") (pin "1-VDD") (pinfunction "VDD_1-VDD") (pintype "power_in"))
      (node (ref "LED85") (pin "1-VDD") (pinfunction "VDD_1-VDD") (pintype "power_in"))
      (node (ref "LED86") (pin "1-VDD") (pinfunction "VDD_1-VDD") (pintype "power_in"))
      (node (ref "LED87") (pin "1-VDD") (pinfunction "VDD_1-VDD") (pintype "power_in"))
      (node (ref "LED88") (pin "1-VDD") (pinfunction "VDD_1-VDD") (pintype "power_in"))
      (node (ref "LED89") (pin "1-VDD") (pinfunction "VDD_1-VDD") (pintype "power_in"))
      (node (ref "LED9") (pin "1-VDD") (pinfunction "VDD_1-VDD") (pintype "power_in"))
      (node (ref "LED90") (pin "1-VDD") (pinfunction "VDD_1-VDD") (pintype "power_in"))
      (node (ref "LED91") (pin "1-VDD") (pinfunction "VDD_1-VDD") (pintype "power_in"))
      (node (ref "LED92") (pin "1-VDD") (pinfunction "VDD_1-VDD") (pintype "power_in"))
      (node (ref "LED93") (pin "1-VDD") (pinfunction "VDD_1-VDD") (pintype "power_in"))
      (node (ref "LED94") (pin "1-VDD") (pinfunction "VDD_1-VDD") (pintype "power_in"))
      (node (ref "LED95") (pin "1-VDD") (pinfunction "VDD_1-VDD") (pintype "power_in"))
      (node (ref "LED96") (pin "1-VDD") (pinfunction "VDD_1-VDD") (pintype "power_in"))
      (node (ref "LED97") (pin "1-VDD") (pinfunction "VDD_1-VDD") (pintype "power_in"))
      (node (ref "LED98") (pin "1-VDD") (pinfunction "VDD_1-VDD") (pintype "power_in"))
      (node (ref "LED99") (pin "1-VDD") (pinfunction "VDD_1-VDD") (pintype "power_in"))
      (node (ref "P1") (pin "3") (pinfunction "3_3") (pintype "passive"))
      (node (ref "P2") (pin "3") (pinfunction "3_3") (pintype "passive"))
    )
  )
)
